# TRS-80.net
KiCad netlist of a schematic drawn in EAGLE
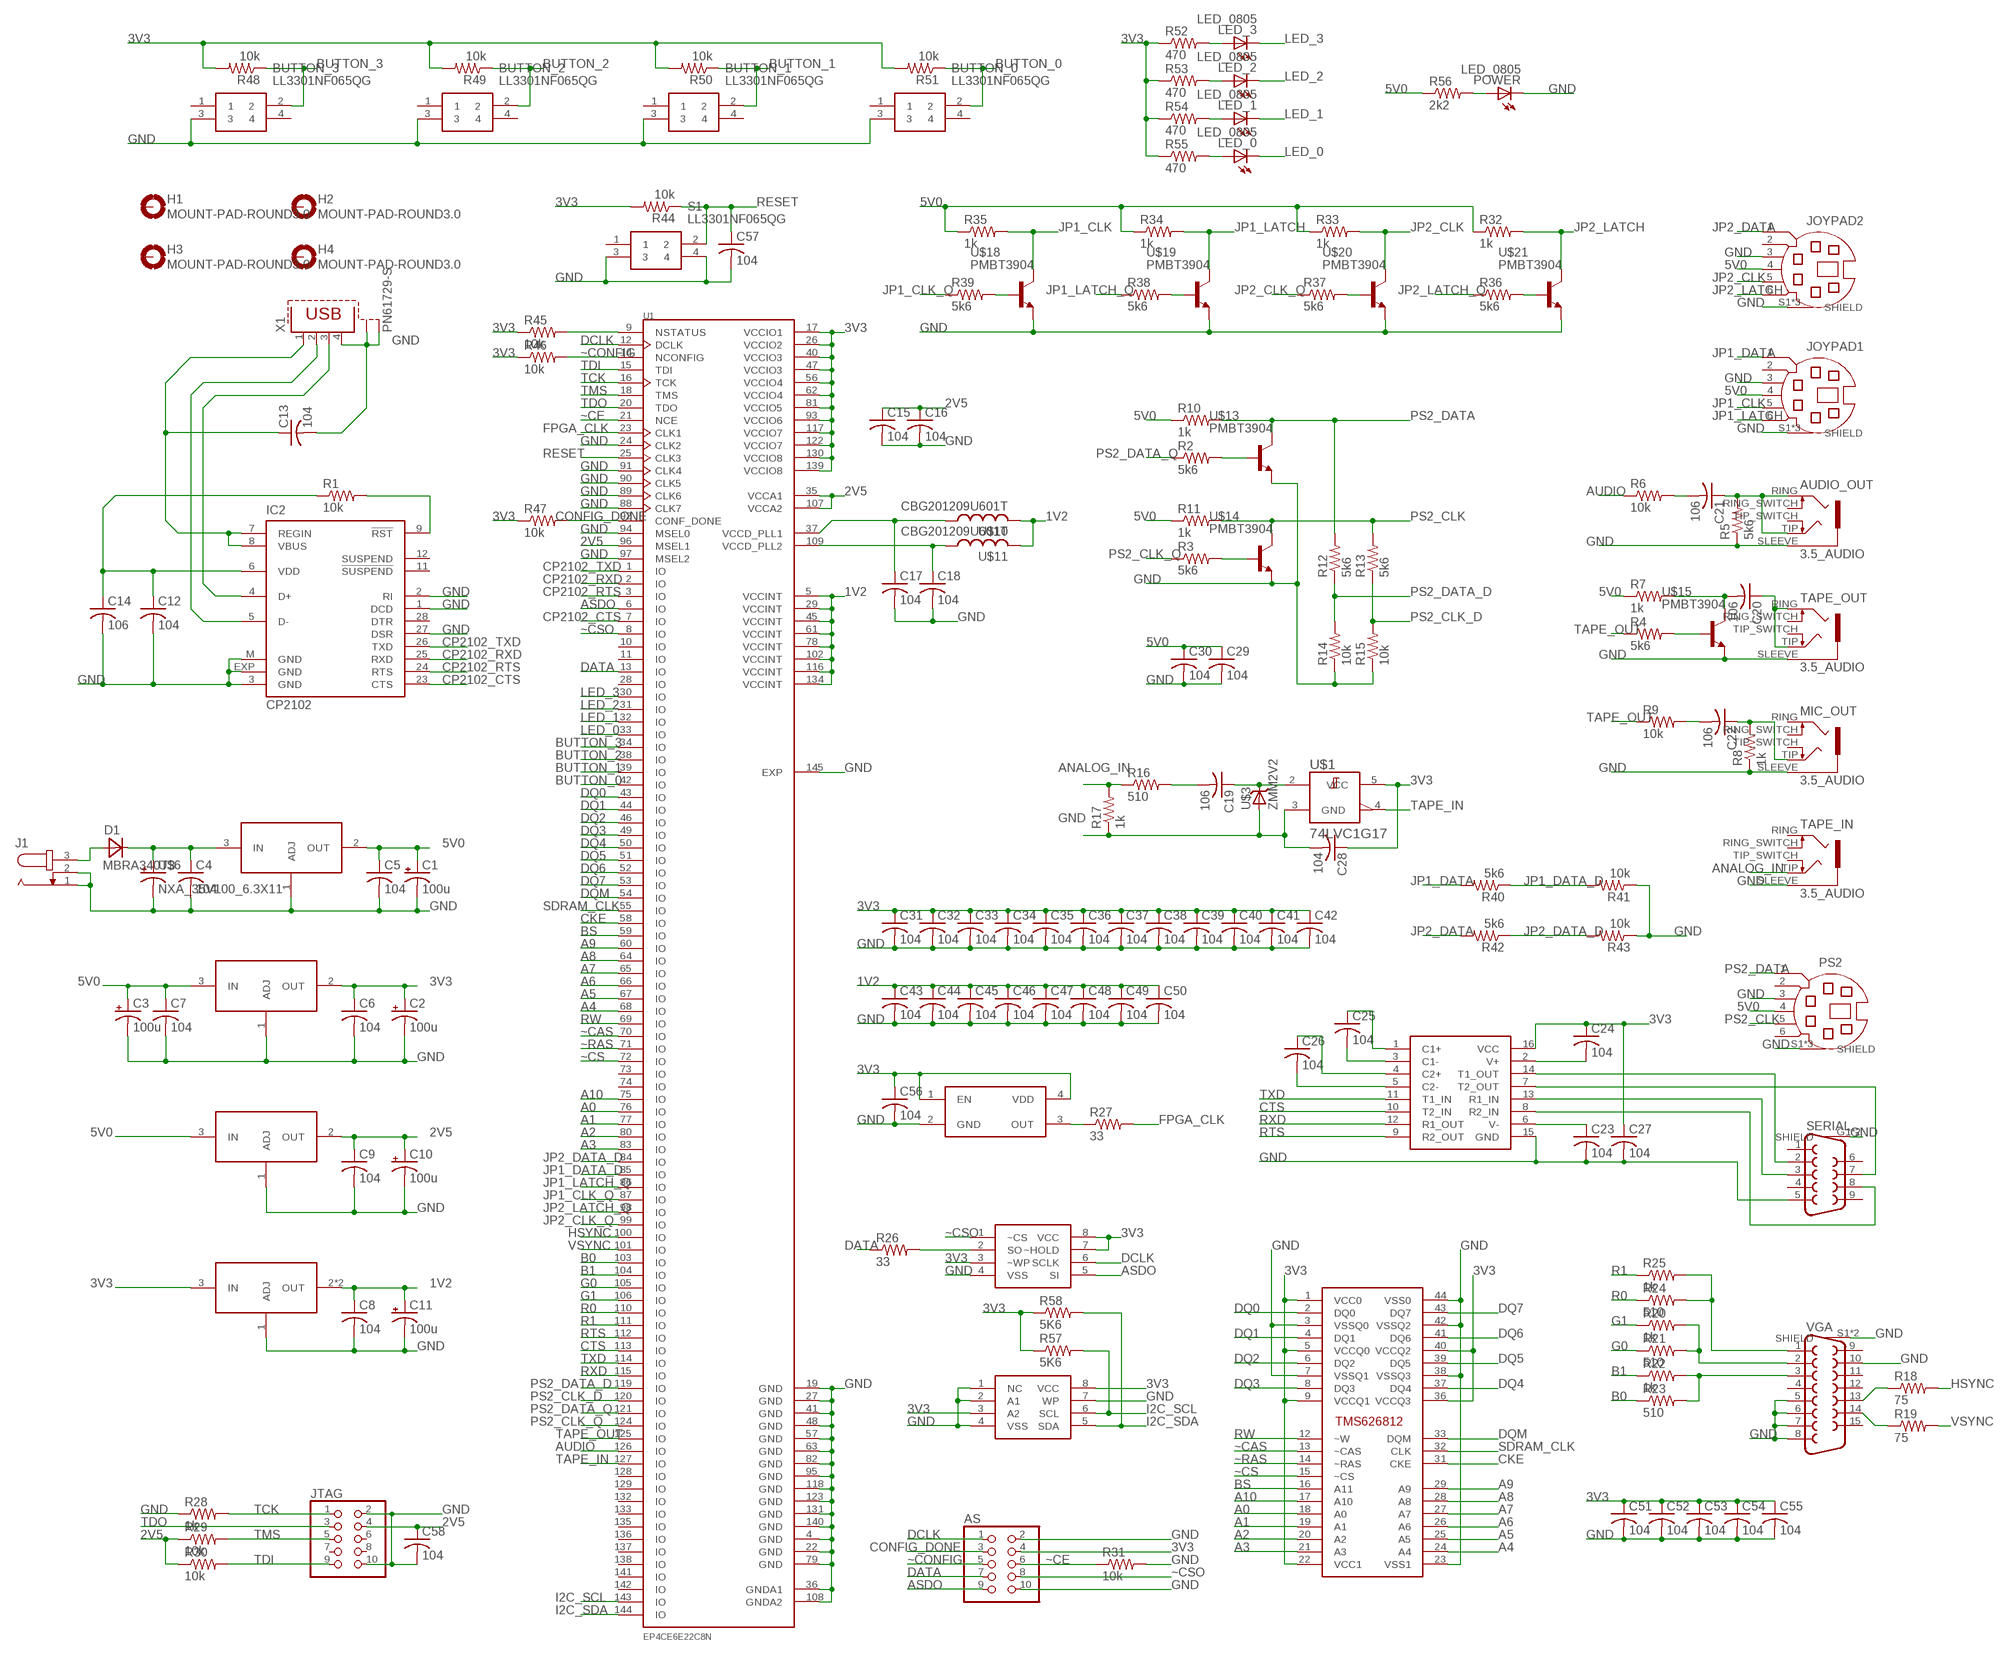
[diagram p0: schematic, sheet 1]

(export (version "E")
  (design (tool "Eeschema 10.0.6"))
  (components
    (comp (ref "AS")
      (value "PINHD-2X5")
      (footprint "eagle-import:2X05")
      (libsource (lib "eagle-import") (part "PINHD-2X5"))
    )
    (comp (ref "AUDIO_OUT")
      (value "3.5_AUDIO")
      (footprint "eagle-import:3.5_AUDIO")
      (libsource (lib "eagle-import") (part "3.5_AUDIO"))
    )
    (comp (ref "BUTTON_0")
      (value "LL3301NF065QG")
      (footprint "eagle-import:LL3301NF065QG")
      (fields (field (name "MOUSER_PART_NUMBER") "612-LL3301NF065QG"))
      (libsource (lib "eagle-import") (part "LL3301NF065QG"))
    )
    (comp (ref "BUTTON_1")
      (value "LL3301NF065QG")
      (footprint "eagle-import:LL3301NF065QG")
      (fields (field (name "MOUSER_PART_NUMBER") "612-LL3301NF065QG"))
      (libsource (lib "eagle-import") (part "LL3301NF065QG"))
    )
    (comp (ref "BUTTON_2")
      (value "LL3301NF065QG")
      (footprint "eagle-import:LL3301NF065QG")
      (fields (field (name "MOUSER_PART_NUMBER") "612-LL3301NF065QG"))
      (libsource (lib "eagle-import") (part "LL3301NF065QG"))
    )
    (comp (ref "BUTTON_3")
      (value "LL3301NF065QG")
      (footprint "eagle-import:LL3301NF065QG")
      (fields (field (name "MOUSER_PART_NUMBER") "612-LL3301NF065QG"))
      (libsource (lib "eagle-import") (part "LL3301NF065QG"))
    )
    (comp (ref "C1")
      (value "100u")
      (footprint "eagle-import:UD-6,3X5,8_NICHICON")
      (libsource (lib "eagle-import") (part "CPOL-USUD-6,3X5,8"))
    )
    (comp (ref "C2")
      (value "100u")
      (footprint "eagle-import:UD-6,3X5,8_NICHICON")
      (libsource (lib "eagle-import") (part "CPOL-USUD-6,3X5,8"))
    )
    (comp (ref "C3")
      (value "100u")
      (footprint "eagle-import:UD-6,3X5,8_NICHICON")
      (libsource (lib "eagle-import") (part "CPOL-USUD-6,3X5,8"))
    )
    (comp (ref "C4")
      (value "104")
      (footprint "eagle-import:C0805")
      (libsource (lib "eagle-import") (part "C-USC0805"))
    )
    (comp (ref "C5")
      (value "104")
      (footprint "eagle-import:C0805")
      (libsource (lib "eagle-import") (part "C-USC0805"))
    )
    (comp (ref "C6")
      (value "104")
      (footprint "eagle-import:C0805")
      (libsource (lib "eagle-import") (part "C-USC0805"))
    )
    (comp (ref "C7")
      (value "104")
      (footprint "eagle-import:C0805")
      (libsource (lib "eagle-import") (part "C-USC0805"))
    )
    (comp (ref "C8")
      (value "104")
      (footprint "eagle-import:C0805")
      (libsource (lib "eagle-import") (part "C-USC0805"))
    )
    (comp (ref "C9")
      (value "104")
      (footprint "eagle-import:C0805")
      (libsource (lib "eagle-import") (part "C-USC0805"))
    )
    (comp (ref "C10")
      (value "100u")
      (footprint "eagle-import:UD-6,3X5,8_NICHICON")
      (libsource (lib "eagle-import") (part "CPOL-USUD-6,3X5,8"))
    )
    (comp (ref "C11")
      (value "100u")
      (footprint "eagle-import:UD-6,3X5,8_NICHICON")
      (libsource (lib "eagle-import") (part "CPOL-USUD-6,3X5,8"))
    )
    (comp (ref "C12")
      (value "104")
      (footprint "eagle-import:C0805")
      (libsource (lib "eagle-import") (part "C-USC0805"))
    )
    (comp (ref "C13")
      (value "104")
      (footprint "eagle-import:C0805")
      (libsource (lib "eagle-import") (part "C-USC0805"))
    )
    (comp (ref "C14")
      (value "106")
      (footprint "eagle-import:C1206")
      (libsource (lib "eagle-import") (part "C-USC1206"))
    )
    (comp (ref "C15")
      (value "104")
      (footprint "eagle-import:C0805")
      (libsource (lib "eagle-import") (part "C-USC0805"))
    )
    (comp (ref "C16")
      (value "104")
      (footprint "eagle-import:C0805")
      (libsource (lib "eagle-import") (part "C-USC0805"))
    )
    (comp (ref "C17")
      (value "104")
      (footprint "eagle-import:C0805")
      (libsource (lib "eagle-import") (part "C-USC0805"))
    )
    (comp (ref "C18")
      (value "104")
      (footprint "eagle-import:C0805")
      (libsource (lib "eagle-import") (part "C-USC0805"))
    )
    (comp (ref "C19")
      (value "106")
      (footprint "eagle-import:C1206")
      (libsource (lib "eagle-import") (part "C-USC1206"))
    )
    (comp (ref "C20")
      (value "106")
      (footprint "eagle-import:C1206")
      (libsource (lib "eagle-import") (part "C-USC1206"))
    )
    (comp (ref "C21")
      (value "106")
      (footprint "eagle-import:C1206")
      (libsource (lib "eagle-import") (part "C-USC1206"))
    )
    (comp (ref "C22")
      (value "106")
      (footprint "eagle-import:C1206")
      (libsource (lib "eagle-import") (part "C-USC1206"))
    )
    (comp (ref "C23")
      (value "104")
      (footprint "eagle-import:C0805")
      (libsource (lib "eagle-import") (part "C-USC0805"))
    )
    (comp (ref "C24")
      (value "104")
      (footprint "eagle-import:C0805")
      (libsource (lib "eagle-import") (part "C-USC0805"))
    )
    (comp (ref "C25")
      (value "104")
      (footprint "eagle-import:C0805")
      (libsource (lib "eagle-import") (part "C-USC0805"))
    )
    (comp (ref "C26")
      (value "104")
      (footprint "eagle-import:C0805")
      (libsource (lib "eagle-import") (part "C-USC0805"))
    )
    (comp (ref "C27")
      (value "104")
      (footprint "eagle-import:C0805")
      (libsource (lib "eagle-import") (part "C-USC0805"))
    )
    (comp (ref "C28")
      (value "104")
      (footprint "eagle-import:C0805")
      (libsource (lib "eagle-import") (part "C-USC0805"))
    )
    (comp (ref "C29")
      (value "104")
      (footprint "eagle-import:C0805")
      (libsource (lib "eagle-import") (part "C-USC0805"))
    )
    (comp (ref "C30")
      (value "104")
      (footprint "eagle-import:C0805")
      (libsource (lib "eagle-import") (part "C-USC0805"))
    )
    (comp (ref "C31")
      (value "104")
      (footprint "eagle-import:C0805")
      (libsource (lib "eagle-import") (part "C-USC0805"))
    )
    (comp (ref "C32")
      (value "104")
      (footprint "eagle-import:C0805")
      (libsource (lib "eagle-import") (part "C-USC0805"))
    )
    (comp (ref "C33")
      (value "104")
      (footprint "eagle-import:C0805")
      (libsource (lib "eagle-import") (part "C-USC0805"))
    )
    (comp (ref "C34")
      (value "104")
      (footprint "eagle-import:C0805")
      (libsource (lib "eagle-import") (part "C-USC0805"))
    )
    (comp (ref "C35")
      (value "104")
      (footprint "eagle-import:C0805")
      (libsource (lib "eagle-import") (part "C-USC0805"))
    )
    (comp (ref "C36")
      (value "104")
      (footprint "eagle-import:C0805")
      (libsource (lib "eagle-import") (part "C-USC0805"))
    )
    (comp (ref "C37")
      (value "104")
      (footprint "eagle-import:C0805")
      (libsource (lib "eagle-import") (part "C-USC0805"))
    )
    (comp (ref "C38")
      (value "104")
      (footprint "eagle-import:C0805")
      (libsource (lib "eagle-import") (part "C-USC0805"))
    )
    (comp (ref "C39")
      (value "104")
      (footprint "eagle-import:C0805")
      (libsource (lib "eagle-import") (part "C-USC0805"))
    )
    (comp (ref "C40")
      (value "104")
      (footprint "eagle-import:C0805")
      (libsource (lib "eagle-import") (part "C-USC0805"))
    )
    (comp (ref "C41")
      (value "104")
      (footprint "eagle-import:C0805")
      (libsource (lib "eagle-import") (part "C-USC0805"))
    )
    (comp (ref "C42")
      (value "104")
      (footprint "eagle-import:C0805")
      (libsource (lib "eagle-import") (part "C-USC0805"))
    )
    (comp (ref "C43")
      (value "104")
      (footprint "eagle-import:C0805")
      (libsource (lib "eagle-import") (part "C-USC0805"))
    )
    (comp (ref "C44")
      (value "104")
      (footprint "eagle-import:C0805")
      (libsource (lib "eagle-import") (part "C-USC0805"))
    )
    (comp (ref "C45")
      (value "104")
      (footprint "eagle-import:C0805")
      (libsource (lib "eagle-import") (part "C-USC0805"))
    )
    (comp (ref "C46")
      (value "104")
      (footprint "eagle-import:C0805")
      (libsource (lib "eagle-import") (part "C-USC0805"))
    )
    (comp (ref "C47")
      (value "104")
      (footprint "eagle-import:C0805")
      (libsource (lib "eagle-import") (part "C-USC0805"))
    )
    (comp (ref "C48")
      (value "104")
      (footprint "eagle-import:C0805")
      (libsource (lib "eagle-import") (part "C-USC0805"))
    )
    (comp (ref "C49")
      (value "104")
      (footprint "eagle-import:C0805")
      (libsource (lib "eagle-import") (part "C-USC0805"))
    )
    (comp (ref "C50")
      (value "104")
      (footprint "eagle-import:C0805")
      (libsource (lib "eagle-import") (part "C-USC0805"))
    )
    (comp (ref "C51")
      (value "104")
      (footprint "eagle-import:C0805")
      (libsource (lib "eagle-import") (part "C-USC0805"))
    )
    (comp (ref "C52")
      (value "104")
      (footprint "eagle-import:C0805")
      (libsource (lib "eagle-import") (part "C-USC0805"))
    )
    (comp (ref "C53")
      (value "104")
      (footprint "eagle-import:C0805")
      (libsource (lib "eagle-import") (part "C-USC0805"))
    )
    (comp (ref "C54")
      (value "104")
      (footprint "eagle-import:C0805")
      (libsource (lib "eagle-import") (part "C-USC0805"))
    )
    (comp (ref "C55")
      (value "104")
      (footprint "eagle-import:C0805")
      (libsource (lib "eagle-import") (part "C-USC0805"))
    )
    (comp (ref "C56")
      (value "104")
      (footprint "eagle-import:C0805")
      (libsource (lib "eagle-import") (part "C-USC0805"))
    )
    (comp (ref "C57")
      (value "104")
      (footprint "eagle-import:C0805")
      (libsource (lib "eagle-import") (part "C-USC0805"))
    )
    (comp (ref "C58")
      (value "104")
      (footprint "eagle-import:C0805")
      (libsource (lib "eagle-import") (part "C-USC0805"))
    )
    (comp (ref "D1")
      (value "MBRA340T3")
      (footprint "eagle-import:SMA")
      (libsource (lib "eagle-import") (part "MBRA340T3"))
    )
    (comp (ref "H1")
      (value "MOUNT-PAD-ROUND3.0")
      (footprint "eagle-import:3,0-PAD")
      (libsource (lib "eagle-import") (part "MOUNT-PAD-ROUND3.0"))
    )
    (comp (ref "H2")
      (value "MOUNT-PAD-ROUND3.0")
      (footprint "eagle-import:3,0-PAD")
      (libsource (lib "eagle-import") (part "MOUNT-PAD-ROUND3.0"))
    )
    (comp (ref "H3")
      (value "MOUNT-PAD-ROUND3.0")
      (footprint "eagle-import:3,0-PAD")
      (libsource (lib "eagle-import") (part "MOUNT-PAD-ROUND3.0"))
    )
    (comp (ref "H4")
      (value "MOUNT-PAD-ROUND3.0")
      (footprint "eagle-import:3,0-PAD")
      (libsource (lib "eagle-import") (part "MOUNT-PAD-ROUND3.0"))
    )
    (comp (ref "IC2")
      (value "CP2102")
      (footprint "eagle-import:MLP28")
      (fields (field (name "MF") "FARNELL") (field (name "MPN") "CP2102-GM"))
      (libsource (lib "eagle-import") (part "CP2102"))
    )
    (comp (ref "J1")
      (value "JACK-PLUG1")
      (footprint "eagle-import:SPC4078")
      (libsource (lib "eagle-import") (part "JACK-PLUG1"))
    )
    (comp (ref "JOYPAD1")
      (value "MD06SS")
      (footprint "eagle-import:MDIN06SS")
      (libsource (lib "eagle-import") (part "MD06SS"))
    )
    (comp (ref "JOYPAD2")
      (value "MD06SS")
      (footprint "eagle-import:MDIN06SS")
      (libsource (lib "eagle-import") (part "MD06SS"))
    )
    (comp (ref "JTAG")
      (value "PINHD-2X5")
      (footprint "eagle-import:2X05")
      (libsource (lib "eagle-import") (part "PINHD-2X5"))
    )
    (comp (ref "LED_0")
      (value "LED_0805")
      (footprint "eagle-import:CHIP-LED0805")
      (libsource (lib "eagle-import") (part "LED_0805"))
    )
    (comp (ref "LED_1")
      (value "LED_0805")
      (footprint "eagle-import:CHIP-LED0805")
      (libsource (lib "eagle-import") (part "LED_0805"))
    )
    (comp (ref "LED_2")
      (value "LED_0805")
      (footprint "eagle-import:CHIP-LED0805")
      (libsource (lib "eagle-import") (part "LED_0805"))
    )
    (comp (ref "LED_3")
      (value "LED_0805")
      (footprint "eagle-import:CHIP-LED0805")
      (libsource (lib "eagle-import") (part "LED_0805"))
    )
    (comp (ref "MIC_OUT")
      (value "3.5_AUDIO")
      (footprint "eagle-import:3.5_AUDIO")
      (libsource (lib "eagle-import") (part "3.5_AUDIO"))
    )
    (comp (ref "POWER")
      (value "LED_0805")
      (footprint "eagle-import:CHIP-LED0805")
      (libsource (lib "eagle-import") (part "LED_0805"))
    )
    (comp (ref "PS2")
      (value "MD06SS")
      (footprint "eagle-import:MDIN06SS")
      (libsource (lib "eagle-import") (part "MD06SS"))
    )
    (comp (ref "R1")
      (value "10k")
      (footprint "eagle-import:R0805")
      (libsource (lib "eagle-import") (part "R-US_R0805"))
    )
    (comp (ref "R2")
      (value "5k6")
      (footprint "eagle-import:R0805")
      (libsource (lib "eagle-import") (part "R-US_R0805"))
    )
    (comp (ref "R3")
      (value "5k6")
      (footprint "eagle-import:R0805")
      (libsource (lib "eagle-import") (part "R-US_R0805"))
    )
    (comp (ref "R4")
      (value "5k6")
      (footprint "eagle-import:R0805")
      (libsource (lib "eagle-import") (part "R-US_R0805"))
    )
    (comp (ref "R5")
      (value "5k6")
      (footprint "eagle-import:R0805")
      (libsource (lib "eagle-import") (part "R-US_R0805"))
    )
    (comp (ref "R6")
      (value "10k")
      (footprint "eagle-import:R0805")
      (libsource (lib "eagle-import") (part "R-US_R0805"))
    )
    (comp (ref "R7")
      (value "1k")
      (footprint "eagle-import:R0805")
      (libsource (lib "eagle-import") (part "R-US_R0805"))
    )
    (comp (ref "R8")
      (value "1k")
      (footprint "eagle-import:R0805")
      (libsource (lib "eagle-import") (part "R-US_R0805"))
    )
    (comp (ref "R9")
      (value "10k")
      (footprint "eagle-import:R0805")
      (libsource (lib "eagle-import") (part "R-US_R0805"))
    )
    (comp (ref "R10")
      (value "1k")
      (footprint "eagle-import:R0805")
      (libsource (lib "eagle-import") (part "R-US_R0805"))
    )
    (comp (ref "R11")
      (value "1k")
      (footprint "eagle-import:R0805")
      (libsource (lib "eagle-import") (part "R-US_R0805"))
    )
    (comp (ref "R12")
      (value "5k6")
      (footprint "eagle-import:R0805")
      (libsource (lib "eagle-import") (part "R-US_R0805"))
    )
    (comp (ref "R13")
      (value "5k6")
      (footprint "eagle-import:R0805")
      (libsource (lib "eagle-import") (part "R-US_R0805"))
    )
    (comp (ref "R14")
      (value "10k")
      (footprint "eagle-import:R0805")
      (libsource (lib "eagle-import") (part "R-US_R0805"))
    )
    (comp (ref "R15")
      (value "10k")
      (footprint "eagle-import:R0805")
      (libsource (lib "eagle-import") (part "R-US_R0805"))
    )
    (comp (ref "R16")
      (value "510")
      (footprint "eagle-import:R0805")
      (libsource (lib "eagle-import") (part "R-US_R0805"))
    )
    (comp (ref "R17")
      (value "1k")
      (footprint "eagle-import:R0805")
      (libsource (lib "eagle-import") (part "R-US_R0805"))
    )
    (comp (ref "R18")
      (value "75")
      (footprint "eagle-import:R0805")
      (libsource (lib "eagle-import") (part "R-US_R0805"))
    )
    (comp (ref "R19")
      (value "75")
      (footprint "eagle-import:R0805")
      (libsource (lib "eagle-import") (part "R-US_R0805"))
    )
    (comp (ref "R20")
      (value "1k")
      (footprint "eagle-import:R0805")
      (libsource (lib "eagle-import") (part "R-US_R0805"))
    )
    (comp (ref "R21")
      (value "510")
      (footprint "eagle-import:R0805")
      (libsource (lib "eagle-import") (part "R-US_R0805"))
    )
    (comp (ref "R22")
      (value "1k")
      (footprint "eagle-import:R0805")
      (libsource (lib "eagle-import") (part "R-US_R0805"))
    )
    (comp (ref "R23")
      (value "510")
      (footprint "eagle-import:R0805")
      (libsource (lib "eagle-import") (part "R-US_R0805"))
    )
    (comp (ref "R24")
      (value "510")
      (footprint "eagle-import:R0805")
      (libsource (lib "eagle-import") (part "R-US_R0805"))
    )
    (comp (ref "R25")
      (value "1k")
      (footprint "eagle-import:R0805")
      (libsource (lib "eagle-import") (part "R-US_R0805"))
    )
    (comp (ref "R26")
      (value "33")
      (footprint "eagle-import:R0805")
      (libsource (lib "eagle-import") (part "R-US_R0805"))
    )
    (comp (ref "R27")
      (value "33")
      (footprint "eagle-import:R0805")
      (libsource (lib "eagle-import") (part "R-US_R0805"))
    )
    (comp (ref "R28")
      (value "1k")
      (footprint "eagle-import:R0805")
      (libsource (lib "eagle-import") (part "R-US_R0805"))
    )
    (comp (ref "R29")
      (value "10k")
      (footprint "eagle-import:R0805")
      (libsource (lib "eagle-import") (part "R-US_R0805"))
    )
    (comp (ref "R30")
      (value "10k")
      (footprint "eagle-import:R0805")
      (libsource (lib "eagle-import") (part "R-US_R0805"))
    )
    (comp (ref "R31")
      (value "10k")
      (footprint "eagle-import:R0805")
      (libsource (lib "eagle-import") (part "R-US_R0805"))
    )
    (comp (ref "R32")
      (value "1k")
      (footprint "eagle-import:R0805")
      (libsource (lib "eagle-import") (part "R-US_R0805"))
    )
    (comp (ref "R33")
      (value "1k")
      (footprint "eagle-import:R0805")
      (libsource (lib "eagle-import") (part "R-US_R0805"))
    )
    (comp (ref "R34")
      (value "1k")
      (footprint "eagle-import:R0805")
      (libsource (lib "eagle-import") (part "R-US_R0805"))
    )
    (comp (ref "R35")
      (value "1k")
      (footprint "eagle-import:R0805")
      (libsource (lib "eagle-import") (part "R-US_R0805"))
    )
    (comp (ref "R36")
      (value "5k6")
      (footprint "eagle-import:R0805")
      (libsource (lib "eagle-import") (part "R-US_R0805"))
    )
    (comp (ref "R37")
      (value "5k6")
      (footprint "eagle-import:R0805")
      (libsource (lib "eagle-import") (part "R-US_R0805"))
    )
    (comp (ref "R38")
      (value "5k6")
      (footprint "eagle-import:R0805")
      (libsource (lib "eagle-import") (part "R-US_R0805"))
    )
    (comp (ref "R39")
      (value "5k6")
      (footprint "eagle-import:R0805")
      (libsource (lib "eagle-import") (part "R-US_R0805"))
    )
    (comp (ref "R40")
      (value "5k6")
      (footprint "eagle-import:R0805")
      (libsource (lib "eagle-import") (part "R-US_R0805"))
    )
    (comp (ref "R41")
      (value "10k")
      (footprint "eagle-import:R0805")
      (libsource (lib "eagle-import") (part "R-US_R0805"))
    )
    (comp (ref "R42")
      (value "5k6")
      (footprint "eagle-import:R0805")
      (libsource (lib "eagle-import") (part "R-US_R0805"))
    )
    (comp (ref "R43")
      (value "10k")
      (footprint "eagle-import:R0805")
      (libsource (lib "eagle-import") (part "R-US_R0805"))
    )
    (comp (ref "R44")
      (value "10k")
      (footprint "eagle-import:R0805")
      (libsource (lib "eagle-import") (part "R-US_R0805"))
    )
    (comp (ref "R45")
      (value "10k")
      (footprint "eagle-import:R0805")
      (libsource (lib "eagle-import") (part "R-US_R0805"))
    )
    (comp (ref "R46")
      (value "10k")
      (footprint "eagle-import:R0805")
      (libsource (lib "eagle-import") (part "R-US_R0805"))
    )
    (comp (ref "R47")
      (value "10k")
      (footprint "eagle-import:R0805")
      (libsource (lib "eagle-import") (part "R-US_R0805"))
    )
    (comp (ref "R48")
      (value "10k")
      (footprint "eagle-import:R0805")
      (libsource (lib "eagle-import") (part "R-US_R0805"))
    )
    (comp (ref "R49")
      (value "10k")
      (footprint "eagle-import:R0805")
      (libsource (lib "eagle-import") (part "R-US_R0805"))
    )
    (comp (ref "R50")
      (value "10k")
      (footprint "eagle-import:R0805")
      (libsource (lib "eagle-import") (part "R-US_R0805"))
    )
    (comp (ref "R51")
      (value "10k")
      (footprint "eagle-import:R0805")
      (libsource (lib "eagle-import") (part "R-US_R0805"))
    )
    (comp (ref "R52")
      (value "470")
      (footprint "eagle-import:R0805")
      (libsource (lib "eagle-import") (part "R-US_R0805"))
    )
    (comp (ref "R53")
      (value "470")
      (footprint "eagle-import:R0805")
      (libsource (lib "eagle-import") (part "R-US_R0805"))
    )
    (comp (ref "R54")
      (value "470")
      (footprint "eagle-import:R0805")
      (libsource (lib "eagle-import") (part "R-US_R0805"))
    )
    (comp (ref "R55")
      (value "470")
      (footprint "eagle-import:R0805")
      (libsource (lib "eagle-import") (part "R-US_R0805"))
    )
    (comp (ref "R56")
      (value "2k2")
      (footprint "eagle-import:R0805")
      (libsource (lib "eagle-import") (part "R-US_R0805"))
    )
    (comp (ref "R57")
      (value "5K6")
      (footprint "eagle-import:R0805")
      (libsource (lib "eagle-import") (part "R-US_R0805"))
    )
    (comp (ref "R58")
      (value "5K6")
      (footprint "eagle-import:R0805")
      (libsource (lib "eagle-import") (part "R-US_R0805"))
    )
    (comp (ref "S1")
      (value "LL3301NF065QG")
      (footprint "eagle-import:LL3301NF065QG")
      (fields (field (name "MOUSER_PART_NUMBER") "612-LL3301NF065QG"))
      (libsource (lib "eagle-import") (part "LL3301NF065QG"))
    )
    (comp (ref "SERIAL")
      (value "F09HP")
      (footprint "eagle-import:F09HP")
      (libsource (lib "eagle-import") (part "F09HP"))
    )
    (comp (ref "TAPE_IN")
      (value "3.5_AUDIO")
      (footprint "eagle-import:3.5_AUDIO")
      (libsource (lib "eagle-import") (part "3.5_AUDIO"))
    )
    (comp (ref "TAPE_OUT")
      (value "3.5_AUDIO")
      (footprint "eagle-import:3.5_AUDIO")
      (libsource (lib "eagle-import") (part "3.5_AUDIO"))
    )
    (comp (ref "U$1")
      (value "74LVC1G17")
      (footprint "eagle-import:SOT353")
      (libsource (lib "eagle-import") (part "74LVC1G17"))
    )
    (comp (ref "U$2")
      (value "TMS626812")
      (footprint "eagle-import:TSOP44-II")
      (libsource (lib "eagle-import") (part "TMS626812"))
    )
    (comp (ref "U$3")
      (value "ZMM2V2")
      (footprint "eagle-import:SOD80C")
      (libsource (lib "eagle-import") (part "ZMM2V2"))
    )
    (comp (ref "U$4")
      (value "SP232")
      (footprint "eagle-import:SOP16")
      (libsource (lib "eagle-import") (part "SP232"))
    )
    (comp (ref "U$5")
      (value "LM1086")
      (footprint "eagle-import:D2PACK")
      (libsource (lib "eagle-import") (part "LM1086"))
    )
    (comp (ref "U$6")
      (value "NXA_35V100_6.3X11")
      (footprint "eagle-import:NXA_35V100_6.3X11")
      (libsource (lib "eagle-import") (part "NXA_35V100_6.3X11"))
    )
    (comp (ref "U$7")
      (value "LD1117D-3.3")
      (footprint "eagle-import:TO252")
      (libsource (lib "eagle-import") (part "LD1117D-3.3"))
    )
    (comp (ref "U$8")
      (value "KIA1117-2.5")
      (footprint "eagle-import:SOT223")
      (libsource (lib "eagle-import") (part "KIA1117-2.5"))
    )
    (comp (ref "U$9")
      (value "AZ1117H-1.2TRG1")
      (footprint "eagle-import:SOT223")
      (libsource (lib "eagle-import") (part "AZ1117H-1.2TRG1"))
    )
    (comp (ref "U$10")
      (value "CBG201209U601T")
      (footprint "eagle-import:C0805")
      (libsource (lib "eagle-import") (part "CBG201209U601T"))
    )
    (comp (ref "U$11")
      (value "CBG201209U601T")
      (footprint "eagle-import:C0805")
      (libsource (lib "eagle-import") (part "CBG201209U601T"))
    )
    (comp (ref "U$12")
      (value "OT705050MJBA4SL")
      (footprint "eagle-import:ASV32000MHZET")
      (libsource (lib "eagle-import") (part "OT705050MJBA4SL"))
    )
    (comp (ref "U$13")
      (value "PMBT3904")
      (footprint "eagle-import:SOT23")
      (libsource (lib "eagle-import") (part "PMBT3904"))
    )
    (comp (ref "U$14")
      (value "PMBT3904")
      (footprint "eagle-import:SOT23")
      (libsource (lib "eagle-import") (part "PMBT3904"))
    )
    (comp (ref "U$15")
      (value "PMBT3904")
      (footprint "eagle-import:SOT23")
      (libsource (lib "eagle-import") (part "PMBT3904"))
    )
    (comp (ref "U$16")
      (value "BY25Q16BS")
      (footprint "eagle-import:SO08")
      (libsource (lib "eagle-import") (part "BY25Q16BS"))
    )
    (comp (ref "U$17")
      (value "CAT24M01WI-GT3")
      (footprint "eagle-import:SO08")
      (libsource (lib "eagle-import") (part "CAT24M01WI-GT3"))
    )
    (comp (ref "U$18")
      (value "PMBT3904")
      (footprint "eagle-import:SOT23")
      (libsource (lib "eagle-import") (part "PMBT3904"))
    )
    (comp (ref "U$19")
      (value "PMBT3904")
      (footprint "eagle-import:SOT23")
      (libsource (lib "eagle-import") (part "PMBT3904"))
    )
    (comp (ref "U$20")
      (value "PMBT3904")
      (footprint "eagle-import:SOT23")
      (libsource (lib "eagle-import") (part "PMBT3904"))
    )
    (comp (ref "U$21")
      (value "PMBT3904")
      (footprint "eagle-import:SOT23")
      (libsource (lib "eagle-import") (part "PMBT3904"))
    )
    (comp (ref "U1")
      (value "EP4CE6E22C8N")
      (footprint "eagle-import:QFP50P2200X2200X165-145N")
      (fields (field (name "MF") "Intel"))
      (libsource (lib "eagle-import") (part "EP4CE6E22C8N"))
    )
    (comp (ref "VGA")
      (value "F15HDH")
      (footprint "eagle-import:HDF15H")
      (libsource (lib "eagle-import") (part "F15HDH"))
    )
    (comp (ref "X1")
      (value "PN61729-S")
      (footprint "eagle-import:PN61729-S")
      (libsource (lib "eagle-import") (part "PN61729-S"))
    )
  )
  (nets
    (net (code "1") (name "/1V2") (class "Default")
      (node (ref "C11") (pin "+") (pinfunction "+_+") (pintype "passive"))
      (node (ref "C43") (pin "1") (pinfunction "1_1") (pintype "passive"))
      (node (ref "C44") (pin "1") (pinfunction "1_1") (pintype "passive"))
      (node (ref "C45") (pin "1") (pinfunction "1_1") (pintype "passive"))
      (node (ref "C46") (pin "1") (pinfunction "1_1") (pintype "passive"))
      (node (ref "C47") (pin "1") (pinfunction "1_1") (pintype "passive"))
      (node (ref "C48") (pin "1") (pinfunction "1_1") (pintype "passive"))
      (node (ref "C49") (pin "1") (pinfunction "1_1") (pintype "passive"))
      (node (ref "C50") (pin "1") (pinfunction "1_1") (pintype "passive"))
      (node (ref "C8") (pin "1") (pinfunction "1_1") (pintype "passive"))
      (node (ref "U$10") (pin "2") (pinfunction "2_2") (pintype "passive"))
      (node (ref "U$11") (pin "2") (pinfunction "2_2") (pintype "passive"))
      (node (ref "U$9") (pin "2") (pinfunction "OUT_2") (pintype "bidirectional"))
      (node (ref "U$9") (pin "4") (pinfunction "OUT_4") (pintype "bidirectional"))
      (node (ref "U1") (pin "102") (pinfunction "VCCINT_102") (pintype "power_in"))
      (node (ref "U1") (pin "116") (pinfunction "VCCINT_116") (pintype "power_in"))
      (node (ref "U1") (pin "134") (pinfunction "VCCINT_134") (pintype "power_in"))
      (node (ref "U1") (pin "29") (pinfunction "VCCINT_29") (pintype "power_in"))
      (node (ref "U1") (pin "45") (pinfunction "VCCINT_45") (pintype "power_in"))
      (node (ref "U1") (pin "5") (pinfunction "VCCINT_5") (pintype "power_in"))
      (node (ref "U1") (pin "61") (pinfunction "VCCINT_61") (pintype "power_in"))
      (node (ref "U1") (pin "78") (pinfunction "VCCINT_78") (pintype "power_in"))
    )
    (net (code "2") (name "/2V5") (class "Default")
      (node (ref "C10") (pin "+") (pinfunction "+_+") (pintype "passive"))
      (node (ref "C15") (pin "1") (pinfunction "1_1") (pintype "passive"))
      (node (ref "C16") (pin "1") (pinfunction "1_1") (pintype "passive"))
      (node (ref "C58") (pin "1") (pinfunction "1_1") (pintype "passive"))
      (node (ref "C9") (pin "1") (pinfunction "1_1") (pintype "passive"))
      (node (ref "JTAG") (pin "4") (pinfunction "4_4") (pintype "passive"))
      (node (ref "R29") (pin "1") (pinfunction "1_1") (pintype "passive"))
      (node (ref "R30") (pin "1") (pinfunction "1_1") (pintype "passive"))
      (node (ref "U$8") (pin "2") (pinfunction "OUT_2") (pintype "bidirectional"))
      (node (ref "U1") (pin "107") (pinfunction "VCCA2_107") (pintype "power_in"))
      (node (ref "U1") (pin "35") (pinfunction "VCCA1_35") (pintype "power_in"))
      (node (ref "U1") (pin "96") (pinfunction "MSEL1_96") (pintype "bidirectional"))
    )
    (net (code "3") (name "/3V3") (class "Default")
      (node (ref "AS") (pin "4") (pinfunction "4_4") (pintype "passive"))
      (node (ref "C2") (pin "+") (pinfunction "+_+") (pintype "passive"))
      (node (ref "C24") (pin "1") (pinfunction "1_1") (pintype "passive"))
      (node (ref "C27") (pin "1") (pinfunction "1_1") (pintype "passive"))
      (node (ref "C28") (pin "1") (pinfunction "1_1") (pintype "passive"))
      (node (ref "C31") (pin "1") (pinfunction "1_1") (pintype "passive"))
      (node (ref "C32") (pin "1") (pinfunction "1_1") (pintype "passive"))
      (node (ref "C33") (pin "1") (pinfunction "1_1") (pintype "passive"))
      (node (ref "C34") (pin "1") (pinfunction "1_1") (pintype "passive"))
      (node (ref "C35") (pin "1") (pinfunction "1_1") (pintype "passive"))
      (node (ref "C36") (pin "1") (pinfunction "1_1") (pintype "passive"))
      (node (ref "C37") (pin "1") (pinfunction "1_1") (pintype "passive"))
      (node (ref "C38") (pin "1") (pinfunction "1_1") (pintype "passive"))
      (node (ref "C39") (pin "1") (pinfunction "1_1") (pintype "passive"))
      (node (ref "C40") (pin "1") (pinfunction "1_1") (pintype "passive"))
      (node (ref "C41") (pin "1") (pinfunction "1_1") (pintype "passive"))
      (node (ref "C42") (pin "1") (pinfunction "1_1") (pintype "passive"))
      (node (ref "C51") (pin "1") (pinfunction "1_1") (pintype "passive"))
      (node (ref "C52") (pin "1") (pinfunction "1_1") (pintype "passive"))
      (node (ref "C53") (pin "1") (pinfunction "1_1") (pintype "passive"))
      (node (ref "C54") (pin "1") (pinfunction "1_1") (pintype "passive"))
      (node (ref "C55") (pin "1") (pinfunction "1_1") (pintype "passive"))
      (node (ref "C56") (pin "1") (pinfunction "1_1") (pintype "passive"))
      (node (ref "C6") (pin "1") (pinfunction "1_1") (pintype "passive"))
      (node (ref "R44") (pin "2") (pinfunction "2_2") (pintype "passive"))
      (node (ref "R45") (pin "1") (pinfunction "1_1") (pintype "passive"))
      (node (ref "R46") (pin "1") (pinfunction "1_1") (pintype "passive"))
      (node (ref "R47") (pin "1") (pinfunction "1_1") (pintype "passive"))
      (node (ref "R48") (pin "2") (pinfunction "2_2") (pintype "passive"))
      (node (ref "R49") (pin "2") (pinfunction "2_2") (pintype "passive"))
      (node (ref "R50") (pin "2") (pinfunction "2_2") (pintype "passive"))
      (node (ref "R51") (pin "2") (pinfunction "2_2") (pintype "passive"))
      (node (ref "R52") (pin "1") (pinfunction "1_1") (pintype "passive"))
      (node (ref "R53") (pin "1") (pinfunction "1_1") (pintype "passive"))
      (node (ref "R54") (pin "1") (pinfunction "1_1") (pintype "passive"))
      (node (ref "R55") (pin "1") (pinfunction "1_1") (pintype "passive"))
      (node (ref "R57") (pin "1") (pinfunction "1_1") (pintype "passive"))
      (node (ref "R58") (pin "1") (pinfunction "1_1") (pintype "passive"))
      (node (ref "U$1") (pin "5") (pinfunction "VCC_5") (pintype "power_in"))
      (node (ref "U$12") (pin "1") (pinfunction "EN_1") (pintype "bidirectional"))
      (node (ref "U$12") (pin "4") (pinfunction "VDD_4") (pintype "bidirectional"))
      (node (ref "U$16") (pin "3") (pinfunction "~{WP}_3") (pintype "bidirectional"))
      (node (ref "U$16") (pin "7") (pinfunction "~{HOLD}_7") (pintype "bidirectional"))
      (node (ref "U$16") (pin "8") (pinfunction "VCC_8") (pintype "bidirectional"))
      (node (ref "U$17") (pin "3") (pinfunction "A2_3") (pintype "bidirectional"))
      (node (ref "U$17") (pin "8") (pinfunction "VCC_8") (pintype "bidirectional"))
      (node (ref "U$2") (pin "1") (pinfunction "VCC0_1") (pintype "bidirectional"))
      (node (ref "U$2") (pin "22") (pinfunction "VCC1_22") (pintype "bidirectional"))
      (node (ref "U$2") (pin "36") (pinfunction "VCCQ3_36") (pintype "bidirectional"))
      (node (ref "U$2") (pin "40") (pinfunction "VCCQ2_40") (pintype "bidirectional"))
      (node (ref "U$2") (pin "5") (pinfunction "VCCQ0_5") (pintype "bidirectional"))
      (node (ref "U$2") (pin "9") (pinfunction "VCCQ1_9") (pintype "bidirectional"))
      (node (ref "U$4") (pin "16") (pinfunction "VCC_16") (pintype "bidirectional"))
      (node (ref "U$7") (pin "2") (pinfunction "OUT_2") (pintype "bidirectional"))
      (node (ref "U$9") (pin "3") (pinfunction "IN_3") (pintype "bidirectional"))
      (node (ref "U1") (pin "117") (pinfunction "VCCIO7_117") (pintype "power_in"))
      (node (ref "U1") (pin "122") (pinfunction "VCCIO7_122") (pintype "power_in"))
      (node (ref "U1") (pin "130") (pinfunction "VCCIO8_130") (pintype "power_in"))
      (node (ref "U1") (pin "139") (pinfunction "VCCIO8_139") (pintype "power_in"))
      (node (ref "U1") (pin "17") (pinfunction "VCCIO1_17") (pintype "power_in"))
      (node (ref "U1") (pin "26") (pinfunction "VCCIO2_26") (pintype "power_in"))
      (node (ref "U1") (pin "40") (pinfunction "VCCIO3_40") (pintype "power_in"))
      (node (ref "U1") (pin "47") (pinfunction "VCCIO3_47") (pintype "power_in"))
      (node (ref "U1") (pin "56") (pinfunction "VCCIO4_56") (pintype "power_in"))
      (node (ref "U1") (pin "62") (pinfunction "VCCIO4_62") (pintype "power_in"))
      (node (ref "U1") (pin "81") (pinfunction "VCCIO5_81") (pintype "power_in"))
      (node (ref "U1") (pin "93") (pinfunction "VCCIO6_93") (pintype "power_in"))
    )
    (net (code "4") (name "/5V0") (class "Default")
      (node (ref "C1") (pin "+") (pinfunction "+_+") (pintype "passive"))
      (node (ref "C29") (pin "1") (pinfunction "1_1") (pintype "passive"))
      (node (ref "C3") (pin "+") (pinfunction "+_+") (pintype "passive"))
      (node (ref "C30") (pin "1") (pinfunction "1_1") (pintype "passive"))
      (node (ref "C5") (pin "1") (pinfunction "1_1") (pintype "passive"))
      (node (ref "C7") (pin "1") (pinfunction "1_1") (pintype "passive"))
      (node (ref "JOYPAD1") (pin "4") (pinfunction "4_4") (pintype "passive"))
      (node (ref "JOYPAD2") (pin "4") (pinfunction "4_4") (pintype "passive"))
      (node (ref "PS2") (pin "4") (pinfunction "4_4") (pintype "passive"))
      (node (ref "R10") (pin "1") (pinfunction "1_1") (pintype "passive"))
      (node (ref "R11") (pin "1") (pinfunction "1_1") (pintype "passive"))
      (node (ref "R32") (pin "1") (pinfunction "1_1") (pintype "passive"))
      (node (ref "R33") (pin "1") (pinfunction "1_1") (pintype "passive"))
      (node (ref "R34") (pin "1") (pinfunction "1_1") (pintype "passive"))
      (node (ref "R35") (pin "1") (pinfunction "1_1") (pintype "passive"))
      (node (ref "R56") (pin "1") (pinfunction "1_1") (pintype "passive"))
      (node (ref "R7") (pin "1") (pinfunction "1_1") (pintype "passive"))
      (node (ref "U$5") (pin "2") (pinfunction "OUT_2") (pintype "bidirectional"))
      (node (ref "U$7") (pin "3") (pinfunction "IN_3") (pintype "bidirectional"))
      (node (ref "U$8") (pin "3") (pinfunction "IN_3") (pintype "bidirectional"))
    )
    (net (code "5") (name "/A0") (class "Default")
      (node (ref "U$2") (pin "18") (pinfunction "A0_18") (pintype "bidirectional"))
      (node (ref "U1") (pin "76") (pinfunction "IO_76") (pintype "bidirectional"))
    )
    (net (code "6") (name "/A1") (class "Default")
      (node (ref "U$2") (pin "19") (pinfunction "A1_19") (pintype "bidirectional"))
      (node (ref "U1") (pin "77") (pinfunction "IO_77") (pintype "bidirectional"))
    )
    (net (code "7") (name "/A2") (class "Default")
      (node (ref "U$2") (pin "20") (pinfunction "A2_20") (pintype "bidirectional"))
      (node (ref "U1") (pin "80") (pinfunction "IO_80") (pintype "bidirectional"))
    )
    (net (code "8") (name "/A3") (class "Default")
      (node (ref "U$2") (pin "21") (pinfunction "A3_21") (pintype "bidirectional"))
      (node (ref "U1") (pin "83") (pinfunction "IO_83") (pintype "bidirectional"))
    )
    (net (code "9") (name "/A4") (class "Default")
      (node (ref "U$2") (pin "24") (pinfunction "A4_24") (pintype "bidirectional"))
      (node (ref "U1") (pin "68") (pinfunction "IO_68") (pintype "bidirectional"))
    )
    (net (code "10") (name "/A5") (class "Default")
      (node (ref "U$2") (pin "25") (pinfunction "A5_25") (pintype "bidirectional"))
      (node (ref "U1") (pin "67") (pinfunction "IO_67") (pintype "bidirectional"))
    )
    (net (code "11") (name "/A6") (class "Default")
      (node (ref "U$2") (pin "26") (pinfunction "A6_26") (pintype "bidirectional"))
      (node (ref "U1") (pin "66") (pinfunction "IO_66") (pintype "bidirectional"))
    )
    (net (code "12") (name "/A7") (class "Default")
      (node (ref "U$2") (pin "27") (pinfunction "A7_27") (pintype "bidirectional"))
      (node (ref "U1") (pin "65") (pinfunction "IO_65") (pintype "bidirectional"))
    )
    (net (code "13") (name "/A8") (class "Default")
      (node (ref "U$2") (pin "28") (pinfunction "A8_28") (pintype "bidirectional"))
      (node (ref "U1") (pin "64") (pinfunction "IO_64") (pintype "bidirectional"))
    )
    (net (code "14") (name "/A9") (class "Default")
      (node (ref "U$2") (pin "29") (pinfunction "A9_29") (pintype "bidirectional"))
      (node (ref "U1") (pin "60") (pinfunction "IO_60") (pintype "bidirectional"))
    )
    (net (code "15") (name "/A10") (class "Default")
      (node (ref "U$2") (pin "17") (pinfunction "A10_17") (pintype "bidirectional"))
      (node (ref "U1") (pin "75") (pinfunction "IO_75") (pintype "bidirectional"))
    )
    (net (code "16") (name "/ANALOG_IN") (class "Default")
      (node (ref "R16") (pin "1") (pinfunction "1_1") (pintype "passive"))
      (node (ref "R17") (pin "2") (pinfunction "2_2") (pintype "passive"))
      (node (ref "TAPE_IN") (pin "TIP") (pinfunction "TIP_TIP") (pintype "passive"))
    )
    (net (code "17") (name "/ASDO") (class "Default")
      (node (ref "AS") (pin "9") (pinfunction "9_9") (pintype "passive"))
      (node (ref "U$16") (pin "5") (pinfunction "SI_5") (pintype "bidirectional"))
      (node (ref "U1") (pin "6") (pinfunction "IO_6") (pintype "bidirectional"))
    )
    (net (code "18") (name "/AUDIO") (class "Default")
      (node (ref "R6") (pin "1") (pinfunction "1_1") (pintype "passive"))
      (node (ref "U1") (pin "126") (pinfunction "IO_126") (pintype "bidirectional"))
    )
    (net (code "19") (name "/B0") (class "Default")
      (node (ref "R23") (pin "1") (pinfunction "1_1") (pintype "passive"))
      (node (ref "U1") (pin "103") (pinfunction "IO_103") (pintype "bidirectional"))
    )
    (net (code "20") (name "/B1") (class "Default")
      (node (ref "R22") (pin "1") (pinfunction "1_1") (pintype "passive"))
      (node (ref "U1") (pin "104") (pinfunction "IO_104") (pintype "bidirectional"))
    )
    (net (code "21") (name "/BS") (class "Default")
      (node (ref "U$2") (pin "16") (pinfunction "A11_16") (pintype "bidirectional"))
      (node (ref "U1") (pin "59") (pinfunction "IO_59") (pintype "bidirectional"))
    )
    (net (code "22") (name "/BUTTON_0") (class "Default")
      (node (ref "BUTTON_0") (pin "2") (pinfunction "2_2") (pintype "bidirectional"))
      (node (ref "R51") (pin "1") (pinfunction "1_1") (pintype "passive"))
      (node (ref "U1") (pin "42") (pinfunction "IO_42") (pintype "bidirectional"))
    )
    (net (code "23") (name "/BUTTON_1") (class "Default")
      (node (ref "BUTTON_1") (pin "2") (pinfunction "2_2") (pintype "bidirectional"))
      (node (ref "R50") (pin "1") (pinfunction "1_1") (pintype "passive"))
      (node (ref "U1") (pin "39") (pinfunction "IO_39") (pintype "bidirectional"))
    )
    (net (code "24") (name "/BUTTON_2") (class "Default")
      (node (ref "BUTTON_2") (pin "2") (pinfunction "2_2") (pintype "bidirectional"))
      (node (ref "R49") (pin "1") (pinfunction "1_1") (pintype "passive"))
      (node (ref "U1") (pin "38") (pinfunction "IO_38") (pintype "bidirectional"))
    )
    (net (code "25") (name "/BUTTON_3") (class "Default")
      (node (ref "BUTTON_3") (pin "2") (pinfunction "2_2") (pintype "bidirectional"))
      (node (ref "R48") (pin "1") (pinfunction "1_1") (pintype "passive"))
      (node (ref "U1") (pin "34") (pinfunction "IO_34") (pintype "bidirectional"))
    )
    (net (code "26") (name "/CKE") (class "Default")
      (node (ref "U$2") (pin "31") (pinfunction "CKE_31") (pintype "bidirectional"))
      (node (ref "U1") (pin "58") (pinfunction "IO_58") (pintype "bidirectional"))
    )
    (net (code "27") (name "/CONFIG_DONE") (class "Default")
      (node (ref "AS") (pin "3") (pinfunction "3_3") (pintype "passive"))
      (node (ref "R47") (pin "2") (pinfunction "2_2") (pintype "passive"))
      (node (ref "U1") (pin "92") (pinfunction "CONF_DONE_92") (pintype "bidirectional"))
    )
    (net (code "28") (name "/CP2102_CTS") (class "Default")
      (node (ref "IC2") (pin "23") (pinfunction "CTS_23") (pintype "input"))
      (node (ref "U1") (pin "7") (pinfunction "IO_7") (pintype "bidirectional"))
    )
    (net (code "29") (name "/CP2102_RTS") (class "Default")
      (node (ref "IC2") (pin "24") (pinfunction "RTS_24") (pintype "output"))
      (node (ref "U1") (pin "3") (pinfunction "IO_3") (pintype "bidirectional"))
    )
    (net (code "30") (name "/CP2102_RXD") (class "Default")
      (node (ref "IC2") (pin "25") (pinfunction "RXD_25") (pintype "input"))
      (node (ref "U1") (pin "2") (pinfunction "IO_2") (pintype "bidirectional"))
    )
    (net (code "31") (name "/CP2102_TXD") (class "Default")
      (node (ref "IC2") (pin "26") (pinfunction "TXD_26") (pintype "output"))
      (node (ref "U1") (pin "1") (pinfunction "IO_1") (pintype "bidirectional"))
    )
    (net (code "32") (name "/CTS") (class "Default")
      (node (ref "U$4") (pin "10") (pinfunction "T2_IN_10") (pintype "bidirectional"))
      (node (ref "U1") (pin "113") (pinfunction "IO_113") (pintype "bidirectional"))
    )
    (net (code "33") (name "/DATA") (class "Default")
      (node (ref "AS") (pin "7") (pinfunction "7_7") (pintype "passive"))
      (node (ref "R26") (pin "1") (pinfunction "1_1") (pintype "passive"))
      (node (ref "U1") (pin "13") (pinfunction "IO_13") (pintype "bidirectional"))
    )
    (net (code "34") (name "/DCLK") (class "Default")
      (node (ref "AS") (pin "1") (pinfunction "1_1") (pintype "passive"))
      (node (ref "U$16") (pin "6") (pinfunction "SCLK_6") (pintype "bidirectional"))
      (node (ref "U1") (pin "12") (pinfunction "DCLK_12") (pintype "bidirectional"))
    )
    (net (code "35") (name "/DQ0") (class "Default")
      (node (ref "U$2") (pin "2") (pinfunction "DQ0_2") (pintype "bidirectional"))
      (node (ref "U1") (pin "43") (pinfunction "IO_43") (pintype "bidirectional"))
    )
    (net (code "36") (name "/DQ1") (class "Default")
      (node (ref "U$2") (pin "4") (pinfunction "DQ1_4") (pintype "bidirectional"))
      (node (ref "U1") (pin "44") (pinfunction "IO_44") (pintype "bidirectional"))
    )
    (net (code "37") (name "/DQ2") (class "Default")
      (node (ref "U$2") (pin "6") (pinfunction "DQ2_6") (pintype "bidirectional"))
      (node (ref "U1") (pin "46") (pinfunction "IO_46") (pintype "bidirectional"))
    )
    (net (code "38") (name "/DQ3") (class "Default")
      (node (ref "U$2") (pin "8") (pinfunction "DQ3_8") (pintype "bidirectional"))
      (node (ref "U1") (pin "49") (pinfunction "IO_49") (pintype "bidirectional"))
    )
    (net (code "39") (name "/DQ4") (class "Default")
      (node (ref "U$2") (pin "37") (pinfunction "DQ4_37") (pintype "bidirectional"))
      (node (ref "U1") (pin "50") (pinfunction "IO_50") (pintype "bidirectional"))
    )
    (net (code "40") (name "/DQ5") (class "Default")
      (node (ref "U$2") (pin "39") (pinfunction "DQ5_39") (pintype "bidirectional"))
      (node (ref "U1") (pin "51") (pinfunction "IO_51") (pintype "bidirectional"))
    )
    (net (code "41") (name "/DQ6") (class "Default")
      (node (ref "U$2") (pin "41") (pinfunction "DQ6_41") (pintype "bidirectional"))
      (node (ref "U1") (pin "52") (pinfunction "IO_52") (pintype "bidirectional"))
    )
    (net (code "42") (name "/DQ7") (class "Default")
      (node (ref "U$2") (pin "43") (pinfunction "DQ7_43") (pintype "bidirectional"))
      (node (ref "U1") (pin "53") (pinfunction "IO_53") (pintype "bidirectional"))
    )
    (net (code "43") (name "/DQM") (class "Default")
      (node (ref "U$2") (pin "33") (pinfunction "DQM_33") (pintype "bidirectional"))
      (node (ref "U1") (pin "54") (pinfunction "IO_54") (pintype "bidirectional"))
    )
    (net (code "44") (name "/FPGA_CLK") (class "Default")
      (node (ref "R27") (pin "2") (pinfunction "2_2") (pintype "passive"))
      (node (ref "U1") (pin "23") (pinfunction "CLK1_23") (pintype "bidirectional"))
    )
    (net (code "45") (name "/G0") (class "Default")
      (node (ref "R21") (pin "1") (pinfunction "1_1") (pintype "passive"))
      (node (ref "U1") (pin "105") (pinfunction "IO_105") (pintype "bidirectional"))
    )
    (net (code "46") (name "/G1") (class "Default")
      (node (ref "R20") (pin "1") (pinfunction "1_1") (pintype "passive"))
      (node (ref "U1") (pin "106") (pinfunction "IO_106") (pintype "bidirectional"))
    )
    (net (code "47") (name "/GND") (class "Default")
      (node (ref "AS") (pin "10") (pinfunction "10_10") (pintype "passive"))
      (node (ref "AS") (pin "2") (pinfunction "2_2") (pintype "passive"))
      (node (ref "AUDIO_OUT") (pin "SLEEVE") (pinfunction "SLEEVE_SLEEVE") (pintype "passive"))
      (node (ref "BUTTON_0") (pin "3") (pinfunction "3_3") (pintype "bidirectional"))
      (node (ref "BUTTON_1") (pin "3") (pinfunction "3_3") (pintype "bidirectional"))
      (node (ref "BUTTON_2") (pin "3") (pinfunction "3_3") (pintype "bidirectional"))
      (node (ref "BUTTON_3") (pin "3") (pinfunction "3_3") (pintype "bidirectional"))
      (node (ref "C1") (pin "-") (pinfunction "-_-") (pintype "passive"))
      (node (ref "C10") (pin "-") (pinfunction "-_-") (pintype "passive"))
      (node (ref "C11") (pin "-") (pinfunction "-_-") (pintype "passive"))
      (node (ref "C12") (pin "2") (pinfunction "2_2") (pintype "passive"))
      (node (ref "C13") (pin "2") (pinfunction "2_2") (pintype "passive"))
      (node (ref "C14") (pin "2") (pinfunction "2_2") (pintype "passive"))
      (node (ref "C15") (pin "2") (pinfunction "2_2") (pintype "passive"))
      (node (ref "C16") (pin "2") (pinfunction "2_2") (pintype "passive"))
      (node (ref "C17") (pin "2") (pinfunction "2_2") (pintype "passive"))
      (node (ref "C18") (pin "2") (pinfunction "2_2") (pintype "passive"))
      (node (ref "C2") (pin "-") (pinfunction "-_-") (pintype "passive"))
      (node (ref "C23") (pin "2") (pinfunction "2_2") (pintype "passive"))
      (node (ref "C27") (pin "2") (pinfunction "2_2") (pintype "passive"))
      (node (ref "C28") (pin "2") (pinfunction "2_2") (pintype "passive"))
      (node (ref "C29") (pin "2") (pinfunction "2_2") (pintype "passive"))
      (node (ref "C3") (pin "-") (pinfunction "-_-") (pintype "passive"))
      (node (ref "C30") (pin "2") (pinfunction "2_2") (pintype "passive"))
      (node (ref "C31") (pin "2") (pinfunction "2_2") (pintype "passive"))
      (node (ref "C32") (pin "2") (pinfunction "2_2") (pintype "passive"))
      (node (ref "C33") (pin "2") (pinfunction "2_2") (pintype "passive"))
      (node (ref "C34") (pin "2") (pinfunction "2_2") (pintype "passive"))
      (node (ref "C35") (pin "2") (pinfunction "2_2") (pintype "passive"))
      (node (ref "C36") (pin "2") (pinfunction "2_2") (pintype "passive"))
      (node (ref "C37") (pin "2") (pinfunction "2_2") (pintype "passive"))
      (node (ref "C38") (pin "2") (pinfunction "2_2") (pintype "passive"))
      (node (ref "C39") (pin "2") (pinfunction "2_2") (pintype "passive"))
      (node (ref "C4") (pin "2") (pinfunction "2_2") (pintype "passive"))
      (node (ref "C40") (pin "2") (pinfunction "2_2") (pintype "passive"))
      (node (ref "C41") (pin "2") (pinfunction "2_2") (pintype "passive"))
      (node (ref "C42") (pin "2") (pinfunction "2_2") (pintype "passive"))
      (node (ref "C43") (pin "2") (pinfunction "2_2") (pintype "passive"))
      (node (ref "C44") (pin "2") (pinfunction "2_2") (pintype "passive"))
      (node (ref "C45") (pin "2") (pinfunction "2_2") (pintype "passive"))
      (node (ref "C46") (pin "2") (pinfunction "2_2") (pintype "passive"))
      (node (ref "C47") (pin "2") (pinfunction "2_2") (pintype "passive"))
      (node (ref "C48") (pin "2") (pinfunction "2_2") (pintype "passive"))
      (node (ref "C49") (pin "2") (pinfunction "2_2") (pintype "passive"))
      (node (ref "C5") (pin "2") (pinfunction "2_2") (pintype "passive"))
      (node (ref "C50") (pin "2") (pinfunction "2_2") (pintype "passive"))
      (node (ref "C51") (pin "2") (pinfunction "2_2") (pintype "passive"))
      (node (ref "C52") (pin "2") (pinfunction "2_2") (pintype "passive"))
      (node (ref "C53") (pin "2") (pinfunction "2_2") (pintype "passive"))
      (node (ref "C54") (pin "2") (pinfunction "2_2") (pintype "passive"))
      (node (ref "C55") (pin "2") (pinfunction "2_2") (pintype "passive"))
      (node (ref "C56") (pin "2") (pinfunction "2_2") (pintype "passive"))
      (node (ref "C57") (pin "2") (pinfunction "2_2") (pintype "passive"))
      (node (ref "C58") (pin "2") (pinfunction "2_2") (pintype "passive"))
      (node (ref "C6") (pin "2") (pinfunction "2_2") (pintype "passive"))
      (node (ref "C7") (pin "2") (pinfunction "2_2") (pintype "passive"))
      (node (ref "C8") (pin "2") (pinfunction "2_2") (pintype "passive"))
      (node (ref "C9") (pin "2") (pinfunction "2_2") (pintype "passive"))
      (node (ref "IC2") (pin "1") (pinfunction "DCD_1") (pintype "input"))
      (node (ref "IC2") (pin "2") (pinfunction "RI_2") (pintype "input"))
      (node (ref "IC2") (pin "27") (pinfunction "DSR_27") (pintype "input"))
      (node (ref "IC2") (pin "3") (pinfunction "GND_3") (pintype "power_in"))
      (node (ref "IC2") (pin "EXP") (pinfunction "GND_EXP") (pintype "power_in"))
      (node (ref "IC2") (pin "M") (pinfunction "GND_M") (pintype "power_in"))
      (node (ref "J1") (pin "1") (pinfunction "1_1") (pintype "passive"))
      (node (ref "J1") (pin "2") (pinfunction "2_2") (pintype "passive"))
      (node (ref "JOYPAD1") (pin "3") (pinfunction "3_3") (pintype "passive"))
      (node (ref "JOYPAD1") (pin "S1") (pinfunction "SHIELD_S1") (pintype "bidirectional"))
      (node (ref "JOYPAD1") (pin "S2") (pinfunction "SHIELD_S2") (pintype "bidirectional"))
      (node (ref "JOYPAD1") (pin "S3") (pinfunction "SHIELD_S3") (pintype "bidirectional"))
      (node (ref "JOYPAD2") (pin "3") (pinfunction "3_3") (pintype "passive"))
      (node (ref "JOYPAD2") (pin "S1") (pinfunction "SHIELD_S1") (pintype "bidirectional"))
      (node (ref "JOYPAD2") (pin "S2") (pinfunction "SHIELD_S2") (pintype "bidirectional"))
      (node (ref "JOYPAD2") (pin "S3") (pinfunction "SHIELD_S3") (pintype "bidirectional"))
      (node (ref "JTAG") (pin "10") (pinfunction "10_10") (pintype "passive"))
      (node (ref "JTAG") (pin "2") (pinfunction "2_2") (pintype "passive"))
      (node (ref "MIC_OUT") (pin "SLEEVE") (pinfunction "SLEEVE_SLEEVE") (pintype "passive"))
      (node (ref "POWER") (pin "C") (pinfunction "C_C") (pintype "passive"))
      (node (ref "PS2") (pin "3") (pinfunction "3_3") (pintype "passive"))
      (node (ref "PS2") (pin "S1") (pinfunction "SHIELD_S1") (pintype "bidirectional"))
      (node (ref "PS2") (pin "S2") (pinfunction "SHIELD_S2") (pintype "bidirectional"))
      (node (ref "PS2") (pin "S3") (pinfunction "SHIELD_S3") (pintype "bidirectional"))
      (node (ref "R14") (pin "1") (pinfunction "1_1") (pintype "passive"))
      (node (ref "R15") (pin "1") (pinfunction "1_1") (pintype "passive"))
      (node (ref "R17") (pin "1") (pinfunction "1_1") (pintype "passive"))
      (node (ref "R28") (pin "1") (pinfunction "1_1") (pintype "passive"))
      (node (ref "R31") (pin "2") (pinfunction "2_2") (pintype "passive"))
      (node (ref "R41") (pin "1") (pinfunction "1_1") (pintype "passive"))
      (node (ref "R43") (pin "1") (pinfunction "1_1") (pintype "passive"))
      (node (ref "R5") (pin "1") (pinfunction "1_1") (pintype "passive"))
      (node (ref "R8") (pin "1") (pinfunction "1_1") (pintype "passive"))
      (node (ref "S1") (pin "3") (pinfunction "3_3") (pintype "bidirectional"))
      (node (ref "S1") (pin "4") (pinfunction "4_4") (pintype "bidirectional"))
      (node (ref "SERIAL") (pin "5") (pinfunction "5_5") (pintype "passive"))
      (node (ref "SERIAL") (pin "G1") (pinfunction "SHIELD_G1") (pintype "bidirectional"))
      (node (ref "SERIAL") (pin "G2") (pinfunction "SHIELD_G2") (pintype "bidirectional"))
      (node (ref "TAPE_IN") (pin "SLEEVE") (pinfunction "SLEEVE_SLEEVE") (pintype "passive"))
      (node (ref "TAPE_OUT") (pin "SLEEVE") (pinfunction "SLEEVE_SLEEVE") (pintype "passive"))
      (node (ref "U$1") (pin "3") (pinfunction "GND_3") (pintype "power_in"))
      (node (ref "U$12") (pin "2") (pinfunction "GND_2") (pintype "bidirectional"))
      (node (ref "U$13") (pin "2") (pinfunction "E_2") (pintype "passive"))
      (node (ref "U$14") (pin "2") (pinfunction "E_2") (pintype "passive"))
      (node (ref "U$15") (pin "2") (pinfunction "E_2") (pintype "passive"))
      (node (ref "U$16") (pin "4") (pinfunction "VSS_4") (pintype "bidirectional"))
      (node (ref "U$17") (pin "1") (pinfunction "NC_1") (pintype "bidirectional"))
      (node (ref "U$17") (pin "2") (pinfunction "A1_2") (pintype "bidirectional"))
      (node (ref "U$17") (pin "4") (pinfunction "VSS_4") (pintype "bidirectional"))
      (node (ref "U$17") (pin "7") (pinfunction "WP_7") (pintype "bidirectional"))
      (node (ref "U$18") (pin "2") (pinfunction "E_2") (pintype "passive"))
      (node (ref "U$19") (pin "2") (pinfunction "E_2") (pintype "passive"))
      (node (ref "U$2") (pin "23") (pinfunction "VSS1_23") (pintype "bidirectional"))
      (node (ref "U$2") (pin "3") (pinfunction "VSSQ0_3") (pintype "bidirectional"))
      (node (ref "U$2") (pin "38") (pinfunction "VSSQ3_38") (pintype "bidirectional"))
      (node (ref "U$2") (pin "42") (pinfunction "VSSQ2_42") (pintype "bidirectional"))
      (node (ref "U$2") (pin "44") (pinfunction "VSS0_44") (pintype "bidirectional"))
      (node (ref "U$2") (pin "7") (pinfunction "VSSQ1_7") (pintype "bidirectional"))
      (node (ref "U$20") (pin "2") (pinfunction "E_2") (pintype "passive"))
      (node (ref "U$21") (pin "2") (pinfunction "E_2") (pintype "passive"))
      (node (ref "U$3") (pin "A") (pinfunction "A_A") (pintype "passive"))
      (node (ref "U$4") (pin "15") (pinfunction "GND_15") (pintype "bidirectional"))
      (node (ref "U$5") (pin "1") (pinfunction "ADJ_1") (pintype "bidirectional"))
      (node (ref "U$6") (pin "P$1") (pinfunction "-_P$1") (pintype "passive"))
      (node (ref "U$7") (pin "1") (pinfunction "ADJ_1") (pintype "bidirectional"))
      (node (ref "U$8") (pin "1") (pinfunction "ADJ_1") (pintype "bidirectional"))
      (node (ref "U$9") (pin "1") (pinfunction "ADJ_1") (pintype "bidirectional"))
      (node (ref "U1") (pin "108") (pinfunction "GNDA2_108") (pintype "power_in"))
      (node (ref "U1") (pin "118") (pinfunction "GND_118") (pintype "power_in"))
      (node (ref "U1") (pin "123") (pinfunction "GND_123") (pintype "power_in"))
      (node (ref "U1") (pin "131") (pinfunction "GND_131") (pintype "power_in"))
      (node (ref "U1") (pin "140") (pinfunction "GND_140") (pintype "power_in"))
      (node (ref "U1") (pin "145") (pinfunction "EXP_145") (pintype "power_in"))
      (node (ref "U1") (pin "19") (pinfunction "GND_19") (pintype "power_in"))
      (node (ref "U1") (pin "22") (pinfunction "GND_22") (pintype "power_in"))
      (node (ref "U1") (pin "24") (pinfunction "CLK2_24") (pintype "bidirectional"))
      (node (ref "U1") (pin "27") (pinfunction "GND_27") (pintype "power_in"))
      (node (ref "U1") (pin "36") (pinfunction "GNDA1_36") (pintype "power_in"))
      (node (ref "U1") (pin "4") (pinfunction "GND_4") (pintype "power_in"))
      (node (ref "U1") (pin "41") (pinfunction "GND_41") (pintype "power_in"))
      (node (ref "U1") (pin "48") (pinfunction "GND_48") (pintype "power_in"))
      (node (ref "U1") (pin "57") (pinfunction "GND_57") (pintype "power_in"))
      (node (ref "U1") (pin "63") (pinfunction "GND_63") (pintype "power_in"))
      (node (ref "U1") (pin "79") (pinfunction "GND_79") (pintype "power_in"))
      (node (ref "U1") (pin "82") (pinfunction "GND_82") (pintype "power_in"))
      (node (ref "U1") (pin "88") (pinfunction "CLK7_88") (pintype "bidirectional"))
      (node (ref "U1") (pin "89") (pinfunction "CLK6_89") (pintype "bidirectional"))
      (node (ref "U1") (pin "90") (pinfunction "CLK5_90") (pintype "bidirectional"))
      (node (ref "U1") (pin "91") (pinfunction "CLK4_91") (pintype "bidirectional"))
      (node (ref "U1") (pin "94") (pinfunction "MSEL0_94") (pintype "bidirectional"))
      (node (ref "U1") (pin "95") (pinfunction "GND_95") (pintype "power_in"))
      (node (ref "U1") (pin "97") (pinfunction "MSEL2_97") (pintype "bidirectional"))
      (node (ref "VGA") (pin "10") (pinfunction "10_10") (pintype "passive"))
      (node (ref "VGA") (pin "5") (pinfunction "5_5") (pintype "passive"))
      (node (ref "VGA") (pin "6") (pinfunction "6_6") (pintype "passive"))
      (node (ref "VGA") (pin "7") (pinfunction "7_7") (pintype "passive"))
      (node (ref "VGA") (pin "8") (pinfunction "8_8") (pintype "passive"))
      (node (ref "VGA") (pin "S1") (pinfunction "SHIELD_S1") (pintype "bidirectional"))
      (node (ref "VGA") (pin "S2") (pinfunction "SHIELD_S2") (pintype "bidirectional"))
      (node (ref "X1") (pin "4") (pinfunction "4_4") (pintype "passive"))
      (node (ref "X1") (pin "S1") (pinfunction "S1_S1") (pintype "passive"))
      (node (ref "X1") (pin "S2") (pinfunction "S2_S2") (pintype "passive"))
    )
    (net (code "48") (name "/HSYNC") (class "Default")
      (node (ref "R18") (pin "2") (pinfunction "2_2") (pintype "passive"))
      (node (ref "U1") (pin "100") (pinfunction "IO_100") (pintype "bidirectional"))
    )
    (net (code "49") (name "/I2C_SCL") (class "Default")
      (node (ref "R57") (pin "2") (pinfunction "2_2") (pintype "passive"))
      (node (ref "U$17") (pin "6") (pinfunction "SCL_6") (pintype "bidirectional"))
      (node (ref "U1") (pin "143") (pinfunction "IO_143") (pintype "bidirectional"))
    )
    (net (code "50") (name "/I2C_SDA") (class "Default")
      (node (ref "R58") (pin "2") (pinfunction "2_2") (pintype "passive"))
      (node (ref "U$17") (pin "5") (pinfunction "SDA_5") (pintype "bidirectional"))
      (node (ref "U1") (pin "144") (pinfunction "IO_144") (pintype "bidirectional"))
    )
    (net (code "51") (name "/JP1_CLK") (class "Default")
      (node (ref "JOYPAD1") (pin "5") (pinfunction "5_5") (pintype "passive"))
      (node (ref "R35") (pin "2") (pinfunction "2_2") (pintype "passive"))
      (node (ref "U$18") (pin "3") (pinfunction "C_3") (pintype "passive"))
    )
    (net (code "52") (name "/JP1_CLK_Q") (class "Default")
      (node (ref "R39") (pin "1") (pinfunction "1_1") (pintype "passive"))
      (node (ref "U1") (pin "87") (pinfunction "IO_87") (pintype "bidirectional"))
    )
    (net (code "53") (name "/JP1_DATA") (class "Default")
      (node (ref "JOYPAD1") (pin "1") (pinfunction "1_1") (pintype "passive"))
      (node (ref "R40") (pin "2") (pinfunction "2_2") (pintype "passive"))
    )
    (net (code "54") (name "/JP1_DATA_D") (class "Default")
      (node (ref "R40") (pin "1") (pinfunction "1_1") (pintype "passive"))
      (node (ref "R41") (pin "2") (pinfunction "2_2") (pintype "passive"))
      (node (ref "U1") (pin "85") (pinfunction "IO_85") (pintype "bidirectional"))
    )
    (net (code "55") (name "/JP1_LATCH") (class "Default")
      (node (ref "JOYPAD1") (pin "6") (pinfunction "6_6") (pintype "passive"))
      (node (ref "R34") (pin "2") (pinfunction "2_2") (pintype "passive"))
      (node (ref "U$19") (pin "3") (pinfunction "C_3") (pintype "passive"))
    )
    (net (code "56") (name "/JP1_LATCH_Q") (class "Default")
      (node (ref "R38") (pin "1") (pinfunction "1_1") (pintype "passive"))
      (node (ref "U1") (pin "86") (pinfunction "IO_86") (pintype "bidirectional"))
    )
    (net (code "57") (name "/JP2_CLK") (class "Default")
      (node (ref "JOYPAD2") (pin "5") (pinfunction "5_5") (pintype "passive"))
      (node (ref "R33") (pin "2") (pinfunction "2_2") (pintype "passive"))
      (node (ref "U$20") (pin "3") (pinfunction "C_3") (pintype "passive"))
    )
    (net (code "58") (name "/JP2_CLK_Q") (class "Default")
      (node (ref "R37") (pin "1") (pinfunction "1_1") (pintype "passive"))
      (node (ref "U1") (pin "99") (pinfunction "IO_99") (pintype "bidirectional"))
    )
    (net (code "59") (name "/JP2_DATA") (class "Default")
      (node (ref "JOYPAD2") (pin "1") (pinfunction "1_1") (pintype "passive"))
      (node (ref "R42") (pin "2") (pinfunction "2_2") (pintype "passive"))
    )
    (net (code "60") (name "/JP2_DATA_D") (class "Default")
      (node (ref "R42") (pin "1") (pinfunction "1_1") (pintype "passive"))
      (node (ref "R43") (pin "2") (pinfunction "2_2") (pintype "passive"))
      (node (ref "U1") (pin "84") (pinfunction "IO_84") (pintype "bidirectional"))
    )
    (net (code "61") (name "/JP2_LATCH") (class "Default")
      (node (ref "JOYPAD2") (pin "6") (pinfunction "6_6") (pintype "passive"))
      (node (ref "R32") (pin "2") (pinfunction "2_2") (pintype "passive"))
      (node (ref "U$21") (pin "3") (pinfunction "C_3") (pintype "passive"))
    )
    (net (code "62") (name "/JP2_LATCH_Q") (class "Default")
      (node (ref "R36") (pin "1") (pinfunction "1_1") (pintype "passive"))
      (node (ref "U1") (pin "98") (pinfunction "IO_98") (pintype "bidirectional"))
    )
    (net (code "63") (name "/LED_0") (class "Default")
      (node (ref "LED_0") (pin "C") (pinfunction "C_C") (pintype "passive"))
      (node (ref "U1") (pin "33") (pinfunction "IO_33") (pintype "bidirectional"))
    )
    (net (code "64") (name "/LED_1") (class "Default")
      (node (ref "LED_1") (pin "C") (pinfunction "C_C") (pintype "passive"))
      (node (ref "U1") (pin "32") (pinfunction "IO_32") (pintype "bidirectional"))
    )
    (net (code "65") (name "/LED_2") (class "Default")
      (node (ref "LED_2") (pin "C") (pinfunction "C_C") (pintype "passive"))
      (node (ref "U1") (pin "31") (pinfunction "IO_31") (pintype "bidirectional"))
    )
    (net (code "66") (name "/LED_3") (class "Default")
      (node (ref "LED_3") (pin "C") (pinfunction "C_C") (pintype "passive"))
      (node (ref "U1") (pin "30") (pinfunction "IO_30") (pintype "bidirectional"))
    )
    (net (code "67") (name "/PS2_CLK") (class "Default")
      (node (ref "PS2") (pin "5") (pinfunction "5_5") (pintype "passive"))
      (node (ref "R11") (pin "2") (pinfunction "2_2") (pintype "passive"))
      (node (ref "R13") (pin "2") (pinfunction "2_2") (pintype "passive"))
      (node (ref "U$14") (pin "3") (pinfunction "C_3") (pintype "passive"))
    )
    (net (code "68") (name "/PS2_CLK_D") (class "Default")
      (node (ref "R13") (pin "1") (pinfunction "1_1") (pintype "passive"))
      (node (ref "R15") (pin "2") (pinfunction "2_2") (pintype "passive"))
      (node (ref "U1") (pin "120") (pinfunction "IO_120") (pintype "bidirectional"))
    )
    (net (code "69") (name "/PS2_CLK_Q") (class "Default")
      (node (ref "R3") (pin "1") (pinfunction "1_1") (pintype "passive"))
      (node (ref "U1") (pin "124") (pinfunction "IO_124") (pintype "bidirectional"))
    )
    (net (code "70") (name "/PS2_DATA") (class "Default")
      (node (ref "PS2") (pin "1") (pinfunction "1_1") (pintype "passive"))
      (node (ref "R10") (pin "2") (pinfunction "2_2") (pintype "passive"))
      (node (ref "R12") (pin "2") (pinfunction "2_2") (pintype "passive"))
      (node (ref "U$13") (pin "3") (pinfunction "C_3") (pintype "passive"))
    )
    (net (code "71") (name "/PS2_DATA_D") (class "Default")
      (node (ref "R12") (pin "1") (pinfunction "1_1") (pintype "passive"))
      (node (ref "R14") (pin "2") (pinfunction "2_2") (pintype "passive"))
      (node (ref "U1") (pin "119") (pinfunction "IO_119") (pintype "bidirectional"))
    )
    (net (code "72") (name "/PS2_DATA_Q") (class "Default")
      (node (ref "R2") (pin "1") (pinfunction "1_1") (pintype "passive"))
      (node (ref "U1") (pin "121") (pinfunction "IO_121") (pintype "bidirectional"))
    )
    (net (code "73") (name "/R0") (class "Default")
      (node (ref "R24") (pin "1") (pinfunction "1_1") (pintype "passive"))
      (node (ref "U1") (pin "110") (pinfunction "IO_110") (pintype "bidirectional"))
    )
    (net (code "74") (name "/R1") (class "Default")
      (node (ref "R25") (pin "1") (pinfunction "1_1") (pintype "passive"))
      (node (ref "U1") (pin "111") (pinfunction "IO_111") (pintype "bidirectional"))
    )
    (net (code "75") (name "/RESET") (class "Default")
      (node (ref "C57") (pin "1") (pinfunction "1_1") (pintype "passive"))
      (node (ref "R44") (pin "1") (pinfunction "1_1") (pintype "passive"))
      (node (ref "S1") (pin "2") (pinfunction "2_2") (pintype "bidirectional"))
      (node (ref "U1") (pin "25") (pinfunction "CLK3_25") (pintype "bidirectional"))
    )
    (net (code "76") (name "/RTS") (class "Default")
      (node (ref "U$4") (pin "9") (pinfunction "R2_OUT_9") (pintype "bidirectional"))
      (node (ref "U1") (pin "112") (pinfunction "IO_112") (pintype "bidirectional"))
    )
    (net (code "77") (name "/RW") (class "Default")
      (node (ref "U$2") (pin "12") (pinfunction "~{W}_12") (pintype "bidirectional"))
      (node (ref "U1") (pin "69") (pinfunction "IO_69") (pintype "bidirectional"))
    )
    (net (code "78") (name "/RXD") (class "Default")
      (node (ref "U$4") (pin "12") (pinfunction "R1_OUT_12") (pintype "bidirectional"))
      (node (ref "U1") (pin "115") (pinfunction "IO_115") (pintype "bidirectional"))
    )
    (net (code "79") (name "/SDRAM_CLK") (class "Default")
      (node (ref "U$2") (pin "32") (pinfunction "CLK_32") (pintype "bidirectional"))
      (node (ref "U1") (pin "55") (pinfunction "IO_55") (pintype "bidirectional"))
    )
    (net (code "80") (name "/TAPE_IN") (class "Default")
      (node (ref "U$1") (pin "4") (pinfunction "Y_4") (pintype "output"))
      (node (ref "U1") (pin "127") (pinfunction "IO_127") (pintype "bidirectional"))
    )
    (net (code "81") (name "/TAPE_OUT") (class "Default")
      (node (ref "R4") (pin "1") (pinfunction "1_1") (pintype "passive"))
      (node (ref "R9") (pin "1") (pinfunction "1_1") (pintype "passive"))
      (node (ref "U1") (pin "125") (pinfunction "IO_125") (pintype "bidirectional"))
    )
    (net (code "82") (name "/TCK") (class "Default")
      (node (ref "JTAG") (pin "1") (pinfunction "1_1") (pintype "passive"))
      (node (ref "R28") (pin "2") (pinfunction "2_2") (pintype "passive"))
      (node (ref "U1") (pin "16") (pinfunction "TCK_16") (pintype "bidirectional"))
    )
    (net (code "83") (name "/TDI") (class "Default")
      (node (ref "JTAG") (pin "9") (pinfunction "9_9") (pintype "passive"))
      (node (ref "R30") (pin "2") (pinfunction "2_2") (pintype "passive"))
      (node (ref "U1") (pin "15") (pinfunction "TDI_15") (pintype "bidirectional"))
    )
    (net (code "84") (name "/TDO") (class "Default")
      (node (ref "JTAG") (pin "3") (pinfunction "3_3") (pintype "passive"))
      (node (ref "U1") (pin "20") (pinfunction "TDO_20") (pintype "bidirectional"))
    )
    (net (code "85") (name "/TMS") (class "Default")
      (node (ref "JTAG") (pin "5") (pinfunction "5_5") (pintype "passive"))
      (node (ref "R29") (pin "2") (pinfunction "2_2") (pintype "passive"))
      (node (ref "U1") (pin "18") (pinfunction "TMS_18") (pintype "bidirectional"))
    )
    (net (code "86") (name "/TXD") (class "Default")
      (node (ref "U$4") (pin "11") (pinfunction "T1_IN_11") (pintype "bidirectional"))
      (node (ref "U1") (pin "114") (pinfunction "IO_114") (pintype "bidirectional"))
    )
    (net (code "87") (name "/VSYNC") (class "Default")
      (node (ref "R19") (pin "2") (pinfunction "2_2") (pintype "passive"))
      (node (ref "U1") (pin "101") (pinfunction "IO_101") (pintype "bidirectional"))
    )
    (net (code "88") (name "/~{CAS}") (class "Default")
      (node (ref "U$2") (pin "13") (pinfunction "~{CAS}_13") (pintype "bidirectional"))
      (node (ref "U1") (pin "70") (pinfunction "IO_70") (pintype "bidirectional"))
    )
    (net (code "89") (name "/~{CE}") (class "Default")
      (node (ref "AS") (pin "6") (pinfunction "6_6") (pintype "passive"))
      (node (ref "R31") (pin "1") (pinfunction "1_1") (pintype "passive"))
      (node (ref "U1") (pin "21") (pinfunction "NCE_21") (pintype "bidirectional"))
    )
    (net (code "90") (name "/~{CONFIG}") (class "Default")
      (node (ref "AS") (pin "5") (pinfunction "5_5") (pintype "passive"))
      (node (ref "R46") (pin "2") (pinfunction "2_2") (pintype "passive"))
      (node (ref "U1") (pin "14") (pinfunction "NCONFIG_14") (pintype "bidirectional"))
    )
    (net (code "91") (name "/~{CSO}") (class "Default")
      (node (ref "AS") (pin "8") (pinfunction "8_8") (pintype "passive"))
      (node (ref "U$16") (pin "1") (pinfunction "~{CS}_1") (pintype "bidirectional"))
      (node (ref "U1") (pin "8") (pinfunction "IO_8") (pintype "bidirectional"))
    )
    (net (code "92") (name "/~{CS}") (class "Default")
      (node (ref "U$2") (pin "15") (pinfunction "~{CS}_15") (pintype "bidirectional"))
      (node (ref "U1") (pin "72") (pinfunction "IO_72") (pintype "bidirectional"))
    )
    (net (code "93") (name "/~{RAS}") (class "Default")
      (node (ref "U$2") (pin "14") (pinfunction "~{RAS}_14") (pintype "bidirectional"))
      (node (ref "U1") (pin "71") (pinfunction "IO_71") (pintype "bidirectional"))
    )
    (net (code "94") (name "Net-(AUDIO_OUT-PadRING)") (class "Default")
      (node (ref "AUDIO_OUT") (pin "RING") (pinfunction "RING_RING") (pintype "passive"))
      (node (ref "AUDIO_OUT") (pin "TIP") (pinfunction "TIP_TIP") (pintype "passive"))
      (node (ref "C21") (pin "1") (pinfunction "1_1") (pintype "passive"))
      (node (ref "R5") (pin "2") (pinfunction "2_2") (pintype "passive"))
    )
    (net (code "95") (name "Net-(C19-Pad2)") (class "Default")
      (node (ref "C19") (pin "2") (pinfunction "2_2") (pintype "passive"))
      (node (ref "R16") (pin "2") (pinfunction "2_2") (pintype "passive"))
    )
    (net (code "96") (name "Net-(C20-Pad1)") (class "Default")
      (node (ref "C20") (pin "1") (pinfunction "1_1") (pintype "passive"))
      (node (ref "TAPE_OUT") (pin "RING") (pinfunction "RING_RING") (pintype "passive"))
      (node (ref "TAPE_OUT") (pin "TIP") (pinfunction "TIP_TIP") (pintype "passive"))
    )
    (net (code "97") (name "Net-(C21-Pad2)") (class "Default")
      (node (ref "C21") (pin "2") (pinfunction "2_2") (pintype "passive"))
      (node (ref "R6") (pin "2") (pinfunction "2_2") (pintype "passive"))
    )
    (net (code "98") (name "Net-(C22-Pad1)") (class "Default")
      (node (ref "C22") (pin "1") (pinfunction "1_1") (pintype "passive"))
      (node (ref "MIC_OUT") (pin "TIP") (pinfunction "TIP_TIP") (pintype "passive"))
      (node (ref "R8") (pin "2") (pinfunction "2_2") (pintype "passive"))
    )
    (net (code "99") (name "Net-(C22-Pad2)") (class "Default")
      (node (ref "C22") (pin "2") (pinfunction "2_2") (pintype "passive"))
      (node (ref "R9") (pin "2") (pinfunction "2_2") (pintype "passive"))
    )
    (net (code "100") (name "Net-(D1-PadA)") (class "Default")
      (node (ref "D1") (pin "A") (pinfunction "A_A") (pintype "passive"))
      (node (ref "J1") (pin "3") (pinfunction "3_3") (pintype "passive"))
    )
    (net (code "101") (name "Net-(IC2-D+)") (class "Default")
      (node (ref "IC2") (pin "4") (pinfunction "D+_4") (pintype "bidirectional"))
      (node (ref "X1") (pin "3") (pinfunction "3_3") (pintype "passive"))
    )
    (net (code "102") (name "Net-(IC2-D-)") (class "Default")
      (node (ref "IC2") (pin "5") (pinfunction "D-_5") (pintype "bidirectional"))
      (node (ref "X1") (pin "2") (pinfunction "2_2") (pintype "passive"))
    )
    (net (code "103") (name "Net-(IC2-REGIN)") (class "Default")
      (node (ref "C13") (pin "1") (pinfunction "1_1") (pintype "passive"))
      (node (ref "IC2") (pin "7") (pinfunction "REGIN_7") (pintype "passive"))
      (node (ref "IC2") (pin "8") (pinfunction "VBUS_8") (pintype "input"))
      (node (ref "X1") (pin "1") (pinfunction "1_1") (pintype "passive"))
    )
    (net (code "104") (name "Net-(IC2-VDD)") (class "Default")
      (node (ref "C12") (pin "1") (pinfunction "1_1") (pintype "passive"))
      (node (ref "C14") (pin "1") (pinfunction "1_1") (pintype "passive"))
      (node (ref "IC2") (pin "6") (pinfunction "VDD_6") (pintype "power_in"))
      (node (ref "R1") (pin "1") (pinfunction "1_1") (pintype "passive"))
    )
    (net (code "105") (name "Net-(IC2-~{RST})") (class "Default")
      (node (ref "IC2") (pin "9") (pinfunction "~{RST}_9") (pintype "bidirectional"))
      (node (ref "R1") (pin "2") (pinfunction "2_2") (pintype "passive"))
    )
    (net (code "106") (name "Net-(LED_0-PadA)") (class "Default")
      (node (ref "LED_0") (pin "A") (pinfunction "A_A") (pintype "passive"))
      (node (ref "R55") (pin "2") (pinfunction "2_2") (pintype "passive"))
    )
    (net (code "107") (name "Net-(LED_1-PadA)") (class "Default")
      (node (ref "LED_1") (pin "A") (pinfunction "A_A") (pintype "passive"))
      (node (ref "R54") (pin "2") (pinfunction "2_2") (pintype "passive"))
    )
    (net (code "108") (name "Net-(LED_2-PadA)") (class "Default")
      (node (ref "LED_2") (pin "A") (pinfunction "A_A") (pintype "passive"))
      (node (ref "R53") (pin "2") (pinfunction "2_2") (pintype "passive"))
    )
    (net (code "109") (name "Net-(LED_3-PadA)") (class "Default")
      (node (ref "LED_3") (pin "A") (pinfunction "A_A") (pintype "passive"))
      (node (ref "R52") (pin "2") (pinfunction "2_2") (pintype "passive"))
    )
    (net (code "110") (name "Net-(POWER-PadA)") (class "Default")
      (node (ref "POWER") (pin "A") (pinfunction "A_A") (pintype "passive"))
      (node (ref "R56") (pin "2") (pinfunction "2_2") (pintype "passive"))
    )
    (net (code "111") (name "Net-(R18-Pad1)") (class "Default")
      (node (ref "R18") (pin "1") (pinfunction "1_1") (pintype "passive"))
      (node (ref "VGA") (pin "13") (pinfunction "13_13") (pintype "passive"))
    )
    (net (code "112") (name "Net-(R19-Pad1)") (class "Default")
      (node (ref "R19") (pin "1") (pinfunction "1_1") (pintype "passive"))
      (node (ref "VGA") (pin "14") (pinfunction "14_14") (pintype "passive"))
    )
    (net (code "113") (name "Net-(R20-Pad2)") (class "Default")
      (node (ref "R20") (pin "2") (pinfunction "2_2") (pintype "passive"))
      (node (ref "R21") (pin "2") (pinfunction "2_2") (pintype "passive"))
      (node (ref "VGA") (pin "2") (pinfunction "2_2") (pintype "passive"))
    )
    (net (code "114") (name "Net-(R22-Pad2)") (class "Default")
      (node (ref "R22") (pin "2") (pinfunction "2_2") (pintype "passive"))
      (node (ref "R23") (pin "2") (pinfunction "2_2") (pintype "passive"))
      (node (ref "VGA") (pin "3") (pinfunction "3_3") (pintype "passive"))
    )
    (net (code "115") (name "Net-(R24-Pad2)") (class "Default")
      (node (ref "R24") (pin "2") (pinfunction "2_2") (pintype "passive"))
      (node (ref "R25") (pin "2") (pinfunction "2_2") (pintype "passive"))
      (node (ref "VGA") (pin "1") (pinfunction "1_1") (pintype "passive"))
    )
    (net (code "116") (name "Net-(U$1-A)") (class "Default")
      (node (ref "C19") (pin "1") (pinfunction "1_1") (pintype "passive"))
      (node (ref "U$1") (pin "2") (pinfunction "A_2") (pintype "input"))
      (node (ref "U$3") (pin "C") (pinfunction "C_C") (pintype "passive"))
    )
    (net (code "117") (name "Net-(U$4-C1+)") (class "Default")
      (node (ref "C25") (pin "1") (pinfunction "1_1") (pintype "passive"))
      (node (ref "U$4") (pin "1") (pinfunction "C1+_1") (pintype "bidirectional"))
    )
    (net (code "118") (name "Net-(U$4-C1-)") (class "Default")
      (node (ref "C25") (pin "2") (pinfunction "2_2") (pintype "passive"))
      (node (ref "U$4") (pin "3") (pinfunction "C1-_3") (pintype "bidirectional"))
    )
    (net (code "119") (name "Net-(U$4-C2+)") (class "Default")
      (node (ref "C26") (pin "1") (pinfunction "1_1") (pintype "passive"))
      (node (ref "U$4") (pin "4") (pinfunction "C2+_4") (pintype "bidirectional"))
    )
    (net (code "120") (name "Net-(U$4-C2-)") (class "Default")
      (node (ref "C26") (pin "2") (pinfunction "2_2") (pintype "passive"))
      (node (ref "U$4") (pin "5") (pinfunction "C2-_5") (pintype "bidirectional"))
    )
    (net (code "121") (name "Net-(U$4-R1_IN)") (class "Default")
      (node (ref "SERIAL") (pin "3") (pinfunction "3_3") (pintype "passive"))
      (node (ref "U$4") (pin "13") (pinfunction "R1_IN_13") (pintype "bidirectional"))
    )
    (net (code "122") (name "Net-(U$4-R2_IN)") (class "Default")
      (node (ref "SERIAL") (pin "8") (pinfunction "8_8") (pintype "passive"))
      (node (ref "U$4") (pin "8") (pinfunction "R2_IN_8") (pintype "bidirectional"))
    )
    (net (code "123") (name "Net-(U$4-T1_OUT)") (class "Default")
      (node (ref "SERIAL") (pin "2") (pinfunction "2_2") (pintype "passive"))
      (node (ref "U$4") (pin "14") (pinfunction "T1_OUT_14") (pintype "bidirectional"))
    )
    (net (code "124") (name "Net-(U$4-T2_OUT)") (class "Default")
      (node (ref "SERIAL") (pin "7") (pinfunction "7_7") (pintype "passive"))
      (node (ref "U$4") (pin "7") (pinfunction "T2_OUT_7") (pintype "bidirectional"))
    )
    (net (code "125") (name "Net-(U$4-V+)") (class "Default")
      (node (ref "C24") (pin "2") (pinfunction "2_2") (pintype "passive"))
      (node (ref "U$4") (pin "2") (pinfunction "V+_2") (pintype "bidirectional"))
    )
    (net (code "126") (name "Net-(U$4-V-)") (class "Default")
      (node (ref "C23") (pin "1") (pinfunction "1_1") (pintype "passive"))
      (node (ref "U$4") (pin "6") (pinfunction "V-_6") (pintype "bidirectional"))
    )
    (net (code "127") (name "Net-(U$5-IN)") (class "Default")
      (node (ref "C4") (pin "1") (pinfunction "1_1") (pintype "passive"))
      (node (ref "D1") (pin "C") (pinfunction "C_C") (pintype "passive"))
      (node (ref "U$5") (pin "3") (pinfunction "IN_3") (pintype "bidirectional"))
      (node (ref "U$6") (pin "P$2") (pinfunction "+_P$2") (pintype "passive"))
    )
    (net (code "128") (name "Net-(U$12-OUT)") (class "Default")
      (node (ref "R27") (pin "1") (pinfunction "1_1") (pintype "passive"))
      (node (ref "U$12") (pin "3") (pinfunction "OUT_3") (pintype "bidirectional"))
    )
    (net (code "129") (name "Net-(U$13-B)") (class "Default")
      (node (ref "R2") (pin "2") (pinfunction "2_2") (pintype "passive"))
      (node (ref "U$13") (pin "1") (pinfunction "B_1") (pintype "passive"))
    )
    (net (code "130") (name "Net-(U$14-B)") (class "Default")
      (node (ref "R3") (pin "2") (pinfunction "2_2") (pintype "passive"))
      (node (ref "U$14") (pin "1") (pinfunction "B_1") (pintype "passive"))
    )
    (net (code "131") (name "Net-(U$15-B)") (class "Default")
      (node (ref "R4") (pin "2") (pinfunction "2_2") (pintype "passive"))
      (node (ref "U$15") (pin "1") (pinfunction "B_1") (pintype "passive"))
    )
    (net (code "132") (name "Net-(U$15-C)") (class "Default")
      (node (ref "C20") (pin "2") (pinfunction "2_2") (pintype "passive"))
      (node (ref "R7") (pin "2") (pinfunction "2_2") (pintype "passive"))
      (node (ref "U$15") (pin "3") (pinfunction "C_3") (pintype "passive"))
    )
    (net (code "133") (name "Net-(U$16-SO)") (class "Default")
      (node (ref "R26") (pin "2") (pinfunction "2_2") (pintype "passive"))
      (node (ref "U$16") (pin "2") (pinfunction "SO_2") (pintype "bidirectional"))
    )
    (net (code "134") (name "Net-(U$18-B)") (class "Default")
      (node (ref "R39") (pin "2") (pinfunction "2_2") (pintype "passive"))
      (node (ref "U$18") (pin "1") (pinfunction "B_1") (pintype "passive"))
    )
    (net (code "135") (name "Net-(U$19-B)") (class "Default")
      (node (ref "R38") (pin "2") (pinfunction "2_2") (pintype "passive"))
      (node (ref "U$19") (pin "1") (pinfunction "B_1") (pintype "passive"))
    )
    (net (code "136") (name "Net-(U$20-B)") (class "Default")
      (node (ref "R37") (pin "2") (pinfunction "2_2") (pintype "passive"))
      (node (ref "U$20") (pin "1") (pinfunction "B_1") (pintype "passive"))
    )
    (net (code "137") (name "Net-(U$21-B)") (class "Default")
      (node (ref "R36") (pin "2") (pinfunction "2_2") (pintype "passive"))
      (node (ref "U$21") (pin "1") (pinfunction "B_1") (pintype "passive"))
    )
    (net (code "138") (name "Net-(U1-NSTATUS)") (class "Default")
      (node (ref "R45") (pin "2") (pinfunction "2_2") (pintype "passive"))
      (node (ref "U1") (pin "9") (pinfunction "NSTATUS_9") (pintype "bidirectional"))
    )
    (net (code "139") (name "Net-(U1-VCCD_PLL1)") (class "Default")
      (node (ref "C17") (pin "1") (pinfunction "1_1") (pintype "passive"))
      (node (ref "U$10") (pin "1") (pinfunction "1_1") (pintype "passive"))
      (node (ref "U1") (pin "37") (pinfunction "VCCD_PLL1_37") (pintype "power_in"))
    )
    (net (code "140") (name "Net-(U1-VCCD_PLL2)") (class "Default")
      (node (ref "C18") (pin "1") (pinfunction "1_1") (pintype "passive"))
      (node (ref "U$11") (pin "1") (pinfunction "1_1") (pintype "passive"))
      (node (ref "U1") (pin "109") (pinfunction "VCCD_PLL2_109") (pintype "power_in"))
    )
    (net (code "141") (name "unconnected-(AUDIO_OUT-PadRING_SWITCH)") (class "Default")
      (node (ref "AUDIO_OUT") (pin "RING_SWITCH") (pinfunction "RING_SWITCH_RING_SWITCH") (pintype "passive"))
    )
    (net (code "142") (name "unconnected-(AUDIO_OUT-PadTIP_SWITCH)") (class "Default")
      (node (ref "AUDIO_OUT") (pin "TIP_SWITCH") (pinfunction "TIP_SWITCH_TIP_SWITCH") (pintype "passive"))
    )
    (net (code "143") (name "unconnected-(BUTTON_0-Pad1)") (class "Default")
      (node (ref "BUTTON_0") (pin "1") (pinfunction "1_1") (pintype "bidirectional"))
    )
    (net (code "144") (name "unconnected-(BUTTON_0-Pad4)") (class "Default")
      (node (ref "BUTTON_0") (pin "4") (pinfunction "4_4") (pintype "bidirectional"))
    )
    (net (code "145") (name "unconnected-(BUTTON_1-Pad1)") (class "Default")
      (node (ref "BUTTON_1") (pin "1") (pinfunction "1_1") (pintype "bidirectional"))
    )
    (net (code "146") (name "unconnected-(BUTTON_1-Pad4)") (class "Default")
      (node (ref "BUTTON_1") (pin "4") (pinfunction "4_4") (pintype "bidirectional"))
    )
    (net (code "147") (name "unconnected-(BUTTON_2-Pad1)") (class "Default")
      (node (ref "BUTTON_2") (pin "1") (pinfunction "1_1") (pintype "bidirectional"))
    )
    (net (code "148") (name "unconnected-(BUTTON_2-Pad4)") (class "Default")
      (node (ref "BUTTON_2") (pin "4") (pinfunction "4_4") (pintype "bidirectional"))
    )
    (net (code "149") (name "unconnected-(BUTTON_3-Pad1)") (class "Default")
      (node (ref "BUTTON_3") (pin "1") (pinfunction "1_1") (pintype "bidirectional"))
    )
    (net (code "150") (name "unconnected-(BUTTON_3-Pad4)") (class "Default")
      (node (ref "BUTTON_3") (pin "4") (pinfunction "4_4") (pintype "bidirectional"))
    )
    (net (code "151") (name "unconnected-(H1-MOUNT-PadB3,0)") (class "Default")
      (node (ref "H1") (pin "B3,0") (pinfunction "MOUNT_B3,0") (pintype "passive"))
    )
    (net (code "152") (name "unconnected-(H2-MOUNT-PadB3,0)") (class "Default")
      (node (ref "H2") (pin "B3,0") (pinfunction "MOUNT_B3,0") (pintype "passive"))
    )
    (net (code "153") (name "unconnected-(H3-MOUNT-PadB3,0)") (class "Default")
      (node (ref "H3") (pin "B3,0") (pinfunction "MOUNT_B3,0") (pintype "passive"))
    )
    (net (code "154") (name "unconnected-(H4-MOUNT-PadB3,0)") (class "Default")
      (node (ref "H4") (pin "B3,0") (pinfunction "MOUNT_B3,0") (pintype "passive"))
    )
    (net (code "155") (name "unconnected-(IC2-DTR-Pad28)") (class "Default")
      (node (ref "IC2") (pin "28") (pinfunction "DTR_28") (pintype "output"))
    )
    (net (code "156") (name "unconnected-(IC2-SUSPEND-Pad12)") (class "Default")
      (node (ref "IC2") (pin "12") (pinfunction "SUSPEND_12") (pintype "output"))
    )
    (net (code "157") (name "unconnected-(IC2-~{SUSPEND}-Pad11)") (class "Default")
      (node (ref "IC2") (pin "11") (pinfunction "~{SUSPEND}_11") (pintype "output"))
    )
    (net (code "158") (name "unconnected-(JOYPAD1-Pad2)") (class "Default")
      (node (ref "JOYPAD1") (pin "2") (pinfunction "2_2") (pintype "passive"))
    )
    (net (code "159") (name "unconnected-(JOYPAD2-Pad2)") (class "Default")
      (node (ref "JOYPAD2") (pin "2") (pinfunction "2_2") (pintype "passive"))
    )
    (net (code "160") (name "unconnected-(JTAG-Pad6)") (class "Default")
      (node (ref "JTAG") (pin "6") (pinfunction "6_6") (pintype "passive"))
    )
    (net (code "161") (name "unconnected-(JTAG-Pad7)") (class "Default")
      (node (ref "JTAG") (pin "7") (pinfunction "7_7") (pintype "passive"))
    )
    (net (code "162") (name "unconnected-(JTAG-Pad8)") (class "Default")
      (node (ref "JTAG") (pin "8") (pinfunction "8_8") (pintype "passive"))
    )
    (net (code "163") (name "unconnected-(MIC_OUT-PadRING)") (class "Default")
      (node (ref "MIC_OUT") (pin "RING") (pinfunction "RING_RING") (pintype "passive"))
    )
    (net (code "164") (name "unconnected-(MIC_OUT-PadRING_SWITCH)") (class "Default")
      (node (ref "MIC_OUT") (pin "RING_SWITCH") (pinfunction "RING_SWITCH_RING_SWITCH") (pintype "passive"))
    )
    (net (code "165") (name "unconnected-(MIC_OUT-PadTIP_SWITCH)") (class "Default")
      (node (ref "MIC_OUT") (pin "TIP_SWITCH") (pinfunction "TIP_SWITCH_TIP_SWITCH") (pintype "passive"))
    )
    (net (code "166") (name "unconnected-(PS2-Pad2)") (class "Default")
      (node (ref "PS2") (pin "2") (pinfunction "2_2") (pintype "passive"))
    )
    (net (code "167") (name "unconnected-(PS2-Pad6)") (class "Default")
      (node (ref "PS2") (pin "6") (pinfunction "6_6") (pintype "passive"))
    )
    (net (code "168") (name "unconnected-(S1-Pad1)") (class "Default")
      (node (ref "S1") (pin "1") (pinfunction "1_1") (pintype "bidirectional"))
    )
    (net (code "169") (name "unconnected-(SERIAL-Pad1)") (class "Default")
      (node (ref "SERIAL") (pin "1") (pinfunction "1_1") (pintype "passive"))
    )
    (net (code "170") (name "unconnected-(SERIAL-Pad4)") (class "Default")
      (node (ref "SERIAL") (pin "4") (pinfunction "4_4") (pintype "passive"))
    )
    (net (code "171") (name "unconnected-(SERIAL-Pad6)") (class "Default")
      (node (ref "SERIAL") (pin "6") (pinfunction "6_6") (pintype "passive"))
    )
    (net (code "172") (name "unconnected-(SERIAL-Pad9)") (class "Default")
      (node (ref "SERIAL") (pin "9") (pinfunction "9_9") (pintype "passive"))
    )
    (net (code "173") (name "unconnected-(TAPE_IN-PadRING)") (class "Default")
      (node (ref "TAPE_IN") (pin "RING") (pinfunction "RING_RING") (pintype "passive"))
    )
    (net (code "174") (name "unconnected-(TAPE_IN-PadRING_SWITCH)") (class "Default")
      (node (ref "TAPE_IN") (pin "RING_SWITCH") (pinfunction "RING_SWITCH_RING_SWITCH") (pintype "passive"))
    )
    (net (code "175") (name "unconnected-(TAPE_IN-PadTIP_SWITCH)") (class "Default")
      (node (ref "TAPE_IN") (pin "TIP_SWITCH") (pinfunction "TIP_SWITCH_TIP_SWITCH") (pintype "passive"))
    )
    (net (code "176") (name "unconnected-(TAPE_OUT-PadRING_SWITCH)") (class "Default")
      (node (ref "TAPE_OUT") (pin "RING_SWITCH") (pinfunction "RING_SWITCH_RING_SWITCH") (pintype "passive"))
    )
    (net (code "177") (name "unconnected-(TAPE_OUT-PadTIP_SWITCH)") (class "Default")
      (node (ref "TAPE_OUT") (pin "TIP_SWITCH") (pinfunction "TIP_SWITCH_TIP_SWITCH") (pintype "passive"))
    )
    (net (code "178") (name "unconnected-(U1-IO-Pad10)") (class "Default")
      (node (ref "U1") (pin "10") (pinfunction "IO_10") (pintype "bidirectional"))
    )
    (net (code "179") (name "unconnected-(U1-IO-Pad11)") (class "Default")
      (node (ref "U1") (pin "11") (pinfunction "IO_11") (pintype "bidirectional"))
    )
    (net (code "180") (name "unconnected-(U1-IO-Pad28)") (class "Default")
      (node (ref "U1") (pin "28") (pinfunction "IO_28") (pintype "bidirectional"))
    )
    (net (code "181") (name "unconnected-(U1-IO-Pad73)") (class "Default")
      (node (ref "U1") (pin "73") (pinfunction "IO_73") (pintype "bidirectional"))
    )
    (net (code "182") (name "unconnected-(U1-IO-Pad74)") (class "Default")
      (node (ref "U1") (pin "74") (pinfunction "IO_74") (pintype "bidirectional"))
    )
    (net (code "183") (name "unconnected-(U1-IO-Pad128)") (class "Default")
      (node (ref "U1") (pin "128") (pinfunction "IO_128") (pintype "bidirectional"))
    )
    (net (code "184") (name "unconnected-(U1-IO-Pad129)") (class "Default")
      (node (ref "U1") (pin "129") (pinfunction "IO_129") (pintype "bidirectional"))
    )
    (net (code "185") (name "unconnected-(U1-IO-Pad132)") (class "Default")
      (node (ref "U1") (pin "132") (pinfunction "IO_132") (pintype "bidirectional"))
    )
    (net (code "186") (name "unconnected-(U1-IO-Pad133)") (class "Default")
      (node (ref "U1") (pin "133") (pinfunction "IO_133") (pintype "bidirectional"))
    )
    (net (code "187") (name "unconnected-(U1-IO-Pad135)") (class "Default")
      (node (ref "U1") (pin "135") (pinfunction "IO_135") (pintype "bidirectional"))
    )
    (net (code "188") (name "unconnected-(U1-IO-Pad136)") (class "Default")
      (node (ref "U1") (pin "136") (pinfunction "IO_136") (pintype "bidirectional"))
    )
    (net (code "189") (name "unconnected-(U1-IO-Pad137)") (class "Default")
      (node (ref "U1") (pin "137") (pinfunction "IO_137") (pintype "bidirectional"))
    )
    (net (code "190") (name "unconnected-(U1-IO-Pad138)") (class "Default")
      (node (ref "U1") (pin "138") (pinfunction "IO_138") (pintype "bidirectional"))
    )
    (net (code "191") (name "unconnected-(U1-IO-Pad141)") (class "Default")
      (node (ref "U1") (pin "141") (pinfunction "IO_141") (pintype "bidirectional"))
    )
    (net (code "192") (name "unconnected-(U1-IO-Pad142)") (class "Default")
      (node (ref "U1") (pin "142") (pinfunction "IO_142") (pintype "bidirectional"))
    )
    (net (code "193") (name "unconnected-(VGA-Pad4)") (class "Default")
      (node (ref "VGA") (pin "4") (pinfunction "4_4") (pintype "passive"))
    )
    (net (code "194") (name "unconnected-(VGA-Pad9)") (class "Default")
      (node (ref "VGA") (pin "9") (pinfunction "9_9") (pintype "passive"))
    )
    (net (code "195") (name "unconnected-(VGA-Pad11)") (class "Default")
      (node (ref "VGA") (pin "11") (pinfunction "11_11") (pintype "passive"))
    )
    (net (code "196") (name "unconnected-(VGA-Pad12)") (class "Default")
      (node (ref "VGA") (pin "12") (pinfunction "12_12") (pintype "passive"))
    )
    (net (code "197") (name "unconnected-(VGA-Pad15)") (class "Default")
      (node (ref "VGA") (pin "15") (pinfunction "15_15") (pintype "passive"))
    )
  )
)
